# VCU_itr2.net
KiCad netlist of a schematic drawn in EAGLE
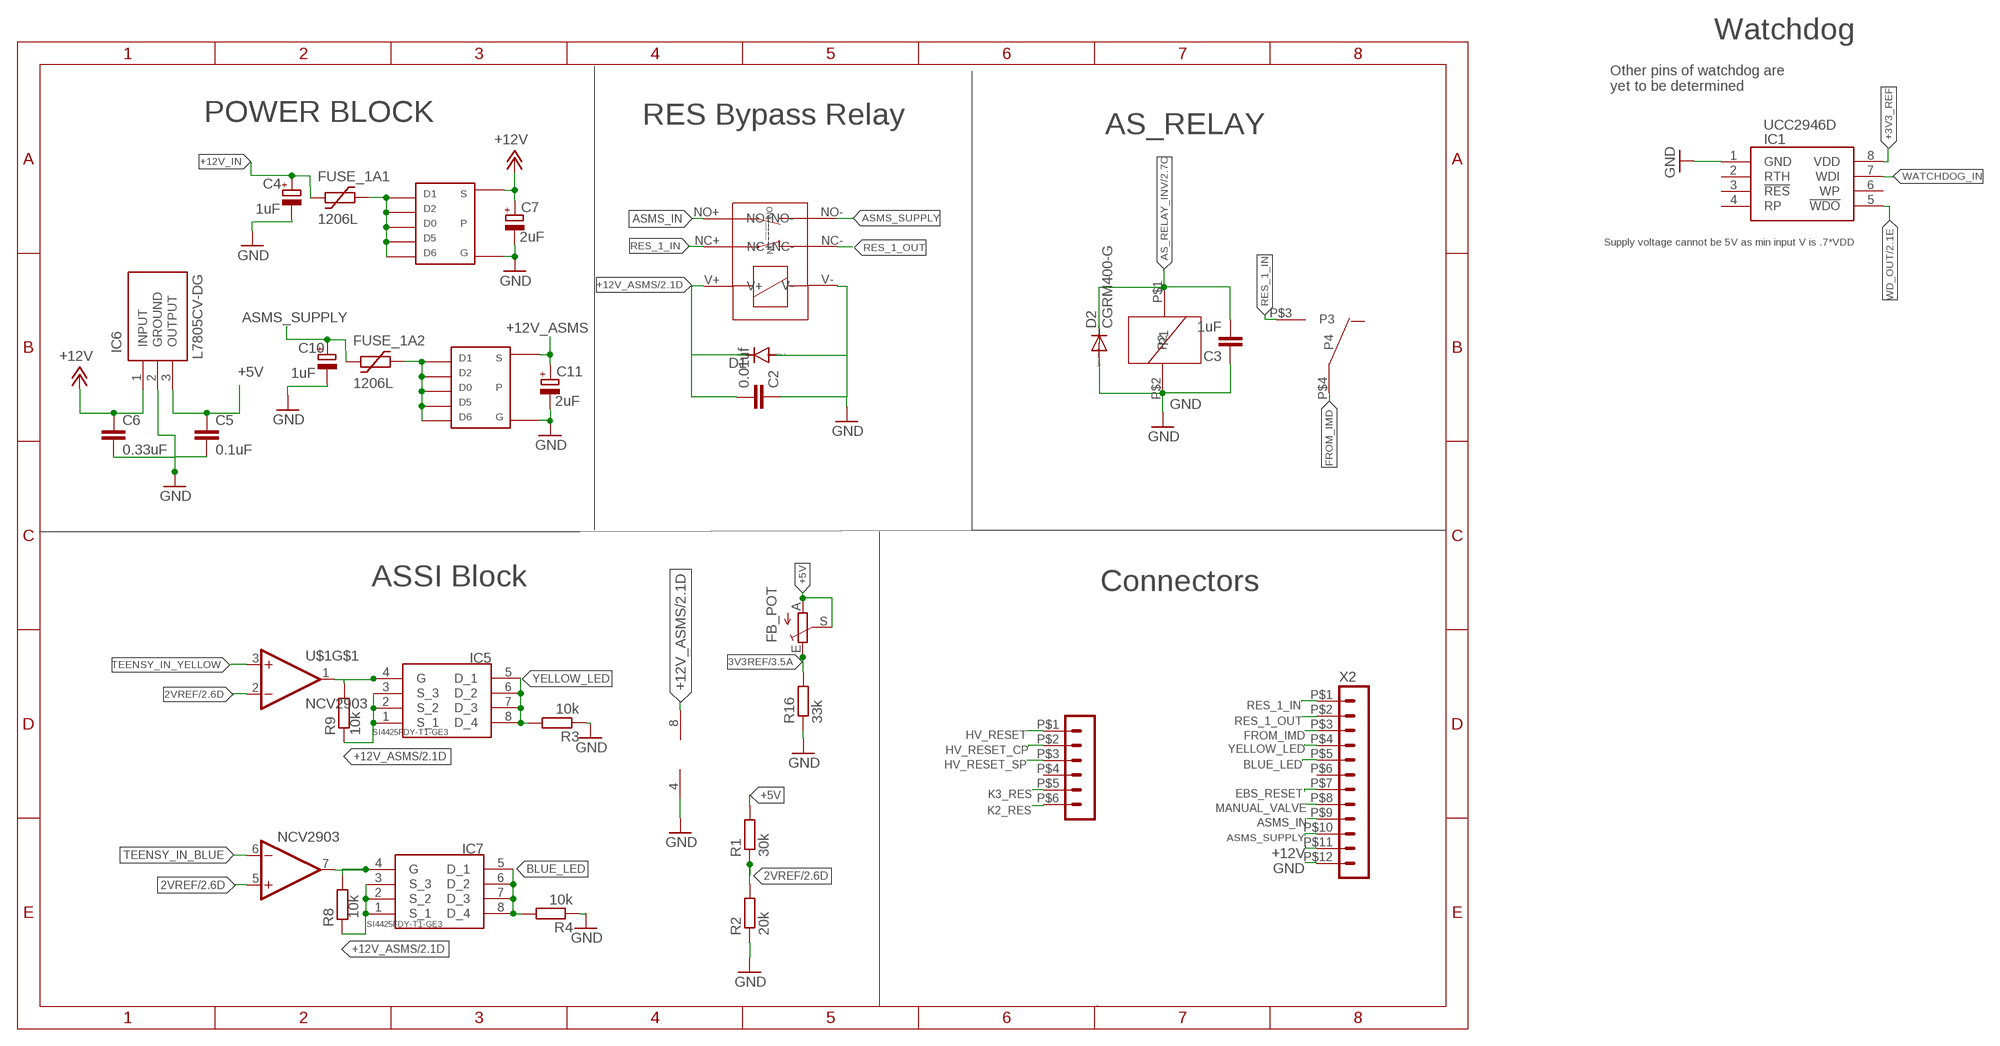
[diagram p0: schematic, sheet 1]
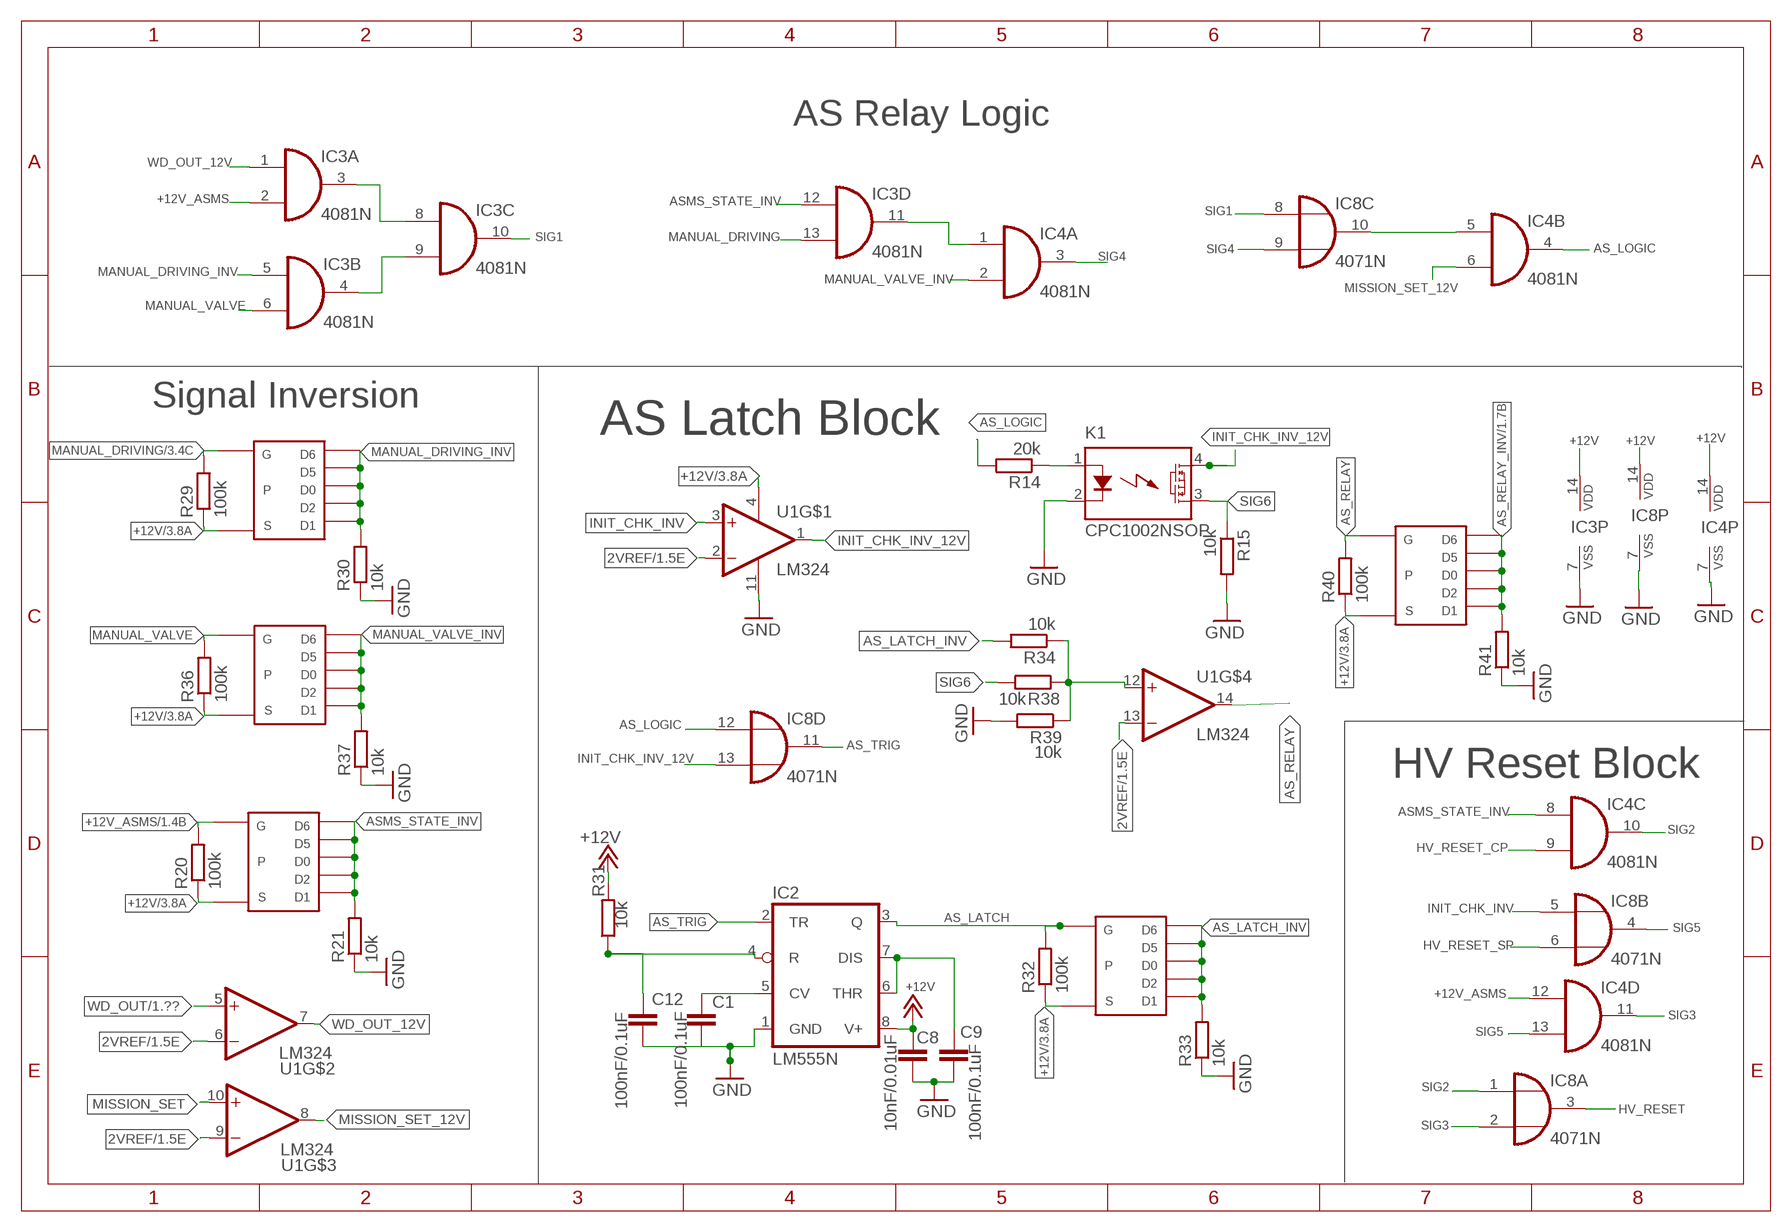
[diagram p1: schematic, sheet 2]
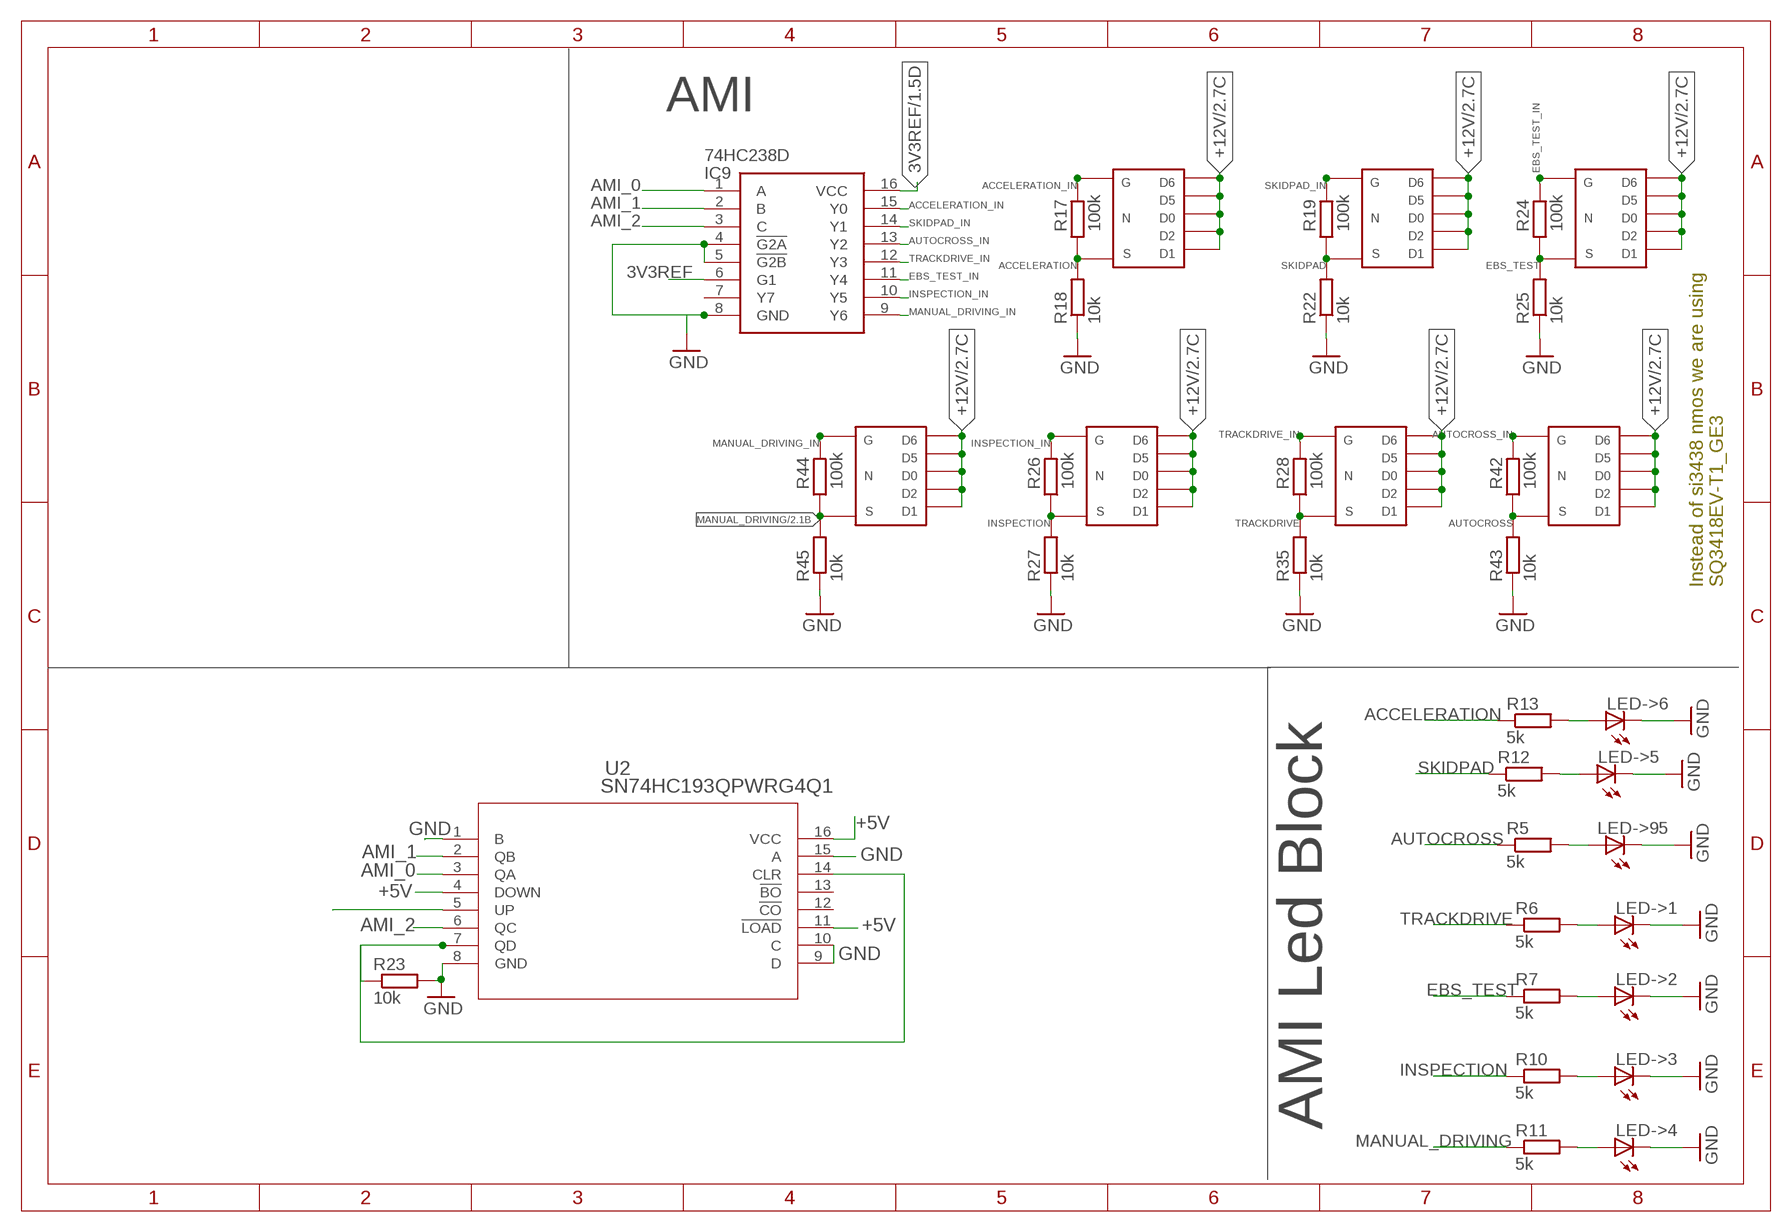
[diagram p2: schematic, sheet 3]
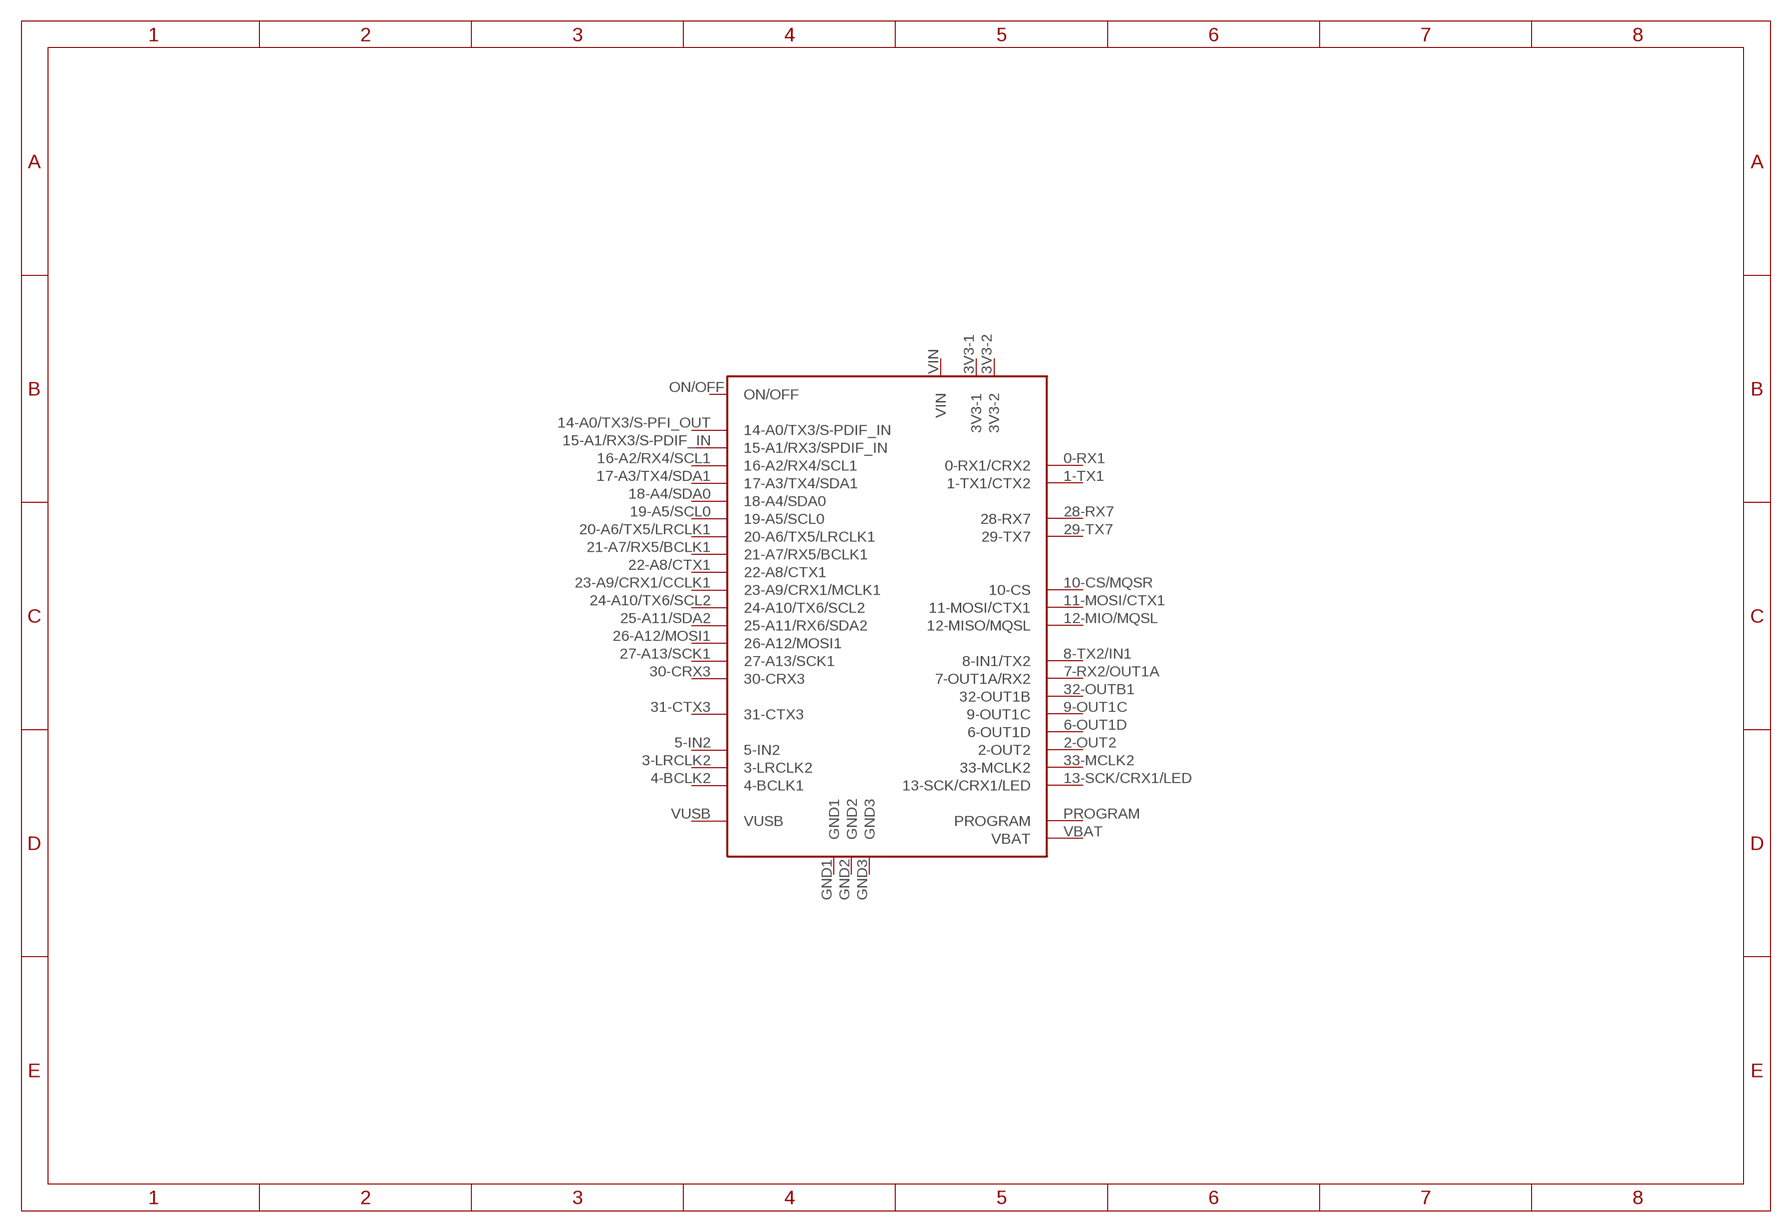
[diagram p3: schematic, sheet 4]

(export (version "E")
  (design (tool "Eeschema 10.0.6"))
  (components
    (comp (ref "IC9")
      (value "74HC238D")
      (footprint "eagle-import:SOIC127P600X175-16N")
      (fields (field (name "MOUSER_PART_NUMBER") "757-74HC238D"))
      (libsource (lib "eagle-import") (part "74HC238D"))
    )
    (comp (ref "LED->1")
      (value "LED-FKIT-1206")
      (footprint "eagle-import:FKIT-LED-1206")
      (libsource (lib "eagle-import") (part "LED-FKIT-1206"))
    )
    (comp (ref "LED->2")
      (value "LED-FKIT-1206")
      (footprint "eagle-import:FKIT-LED-1206")
      (libsource (lib "eagle-import") (part "LED-FKIT-1206"))
    )
    (comp (ref "LED->3")
      (value "LED-FKIT-1206")
      (footprint "eagle-import:FKIT-LED-1206")
      (libsource (lib "eagle-import") (part "LED-FKIT-1206"))
    )
    (comp (ref "LED->4")
      (value "LED-FKIT-1206")
      (footprint "eagle-import:FKIT-LED-1206")
      (libsource (lib "eagle-import") (part "LED-FKIT-1206"))
    )
    (comp (ref "LED->5")
      (value "LED-FKIT-1206")
      (footprint "eagle-import:FKIT-LED-1206")
      (libsource (lib "eagle-import") (part "LED-FKIT-1206"))
    )
    (comp (ref "LED->6")
      (value "LED-FKIT-1206")
      (footprint "eagle-import:FKIT-LED-1206")
      (libsource (lib "eagle-import") (part "LED-FKIT-1206"))
    )
    (comp (ref "LED->95")
      (value "LED-FKIT-1206")
      (footprint "eagle-import:FKIT-LED-1206")
      (libsource (lib "eagle-import") (part "LED-FKIT-1206"))
    )
    (comp (ref "R5")
      (value "5k")
      (footprint "eagle-import:R0805")
      (libsource (lib "eagle-import") (part "R-EU_R0805"))
    )
    (comp (ref "R6")
      (value "5k")
      (footprint "eagle-import:R0805")
      (libsource (lib "eagle-import") (part "R-EU_R0805"))
    )
    (comp (ref "R7")
      (value "5k")
      (footprint "eagle-import:R0805")
      (libsource (lib "eagle-import") (part "R-EU_R0805"))
    )
    (comp (ref "R10")
      (value "5k")
      (footprint "eagle-import:R0805")
      (libsource (lib "eagle-import") (part "R-EU_R0805"))
    )
    (comp (ref "R11")
      (value "5k")
      (footprint "eagle-import:R0805")
      (libsource (lib "eagle-import") (part "R-EU_R0805"))
    )
    (comp (ref "R12")
      (value "5k")
      (footprint "eagle-import:R0805")
      (libsource (lib "eagle-import") (part "R-EU_R0805"))
    )
    (comp (ref "R13")
      (value "5k")
      (footprint "eagle-import:R0805")
      (libsource (lib "eagle-import") (part "R-EU_R0805"))
    )
    (comp (ref "R17")
      (value "100k")
      (footprint "eagle-import:R0805")
      (libsource (lib "eagle-import") (part "R-EU_R0805"))
    )
    (comp (ref "R18")
      (value "10k")
      (footprint "eagle-import:M0805")
      (libsource (lib "eagle-import") (part "IIT_BOMBAY_Racing2_R-EU_M0805"))
    )
    (comp (ref "R19")
      (value "100k")
      (footprint "eagle-import:R0805")
      (libsource (lib "eagle-import") (part "R-EU_R0805"))
    )
    (comp (ref "R22")
      (value "10k")
      (footprint "eagle-import:M0805")
      (libsource (lib "eagle-import") (part "IIT_BOMBAY_Racing2_R-EU_M0805"))
    )
    (comp (ref "R23")
      (value "10k")
      (footprint "eagle-import:M0805")
      (libsource (lib "eagle-import") (part "IIT_BOMBAY_Racing2_R-EU_M0805"))
    )
    (comp (ref "R24")
      (value "100k")
      (footprint "eagle-import:R0805")
      (libsource (lib "eagle-import") (part "R-EU_R0805"))
    )
    (comp (ref "R25")
      (value "10k")
      (footprint "eagle-import:M0805")
      (libsource (lib "eagle-import") (part "IIT_BOMBAY_Racing2_R-EU_M0805"))
    )
    (comp (ref "R26")
      (value "100k")
      (footprint "eagle-import:R0805")
      (libsource (lib "eagle-import") (part "R-EU_R0805"))
    )
    (comp (ref "R27")
      (value "10k")
      (footprint "eagle-import:M0805")
      (libsource (lib "eagle-import") (part "IIT_BOMBAY_Racing2_R-EU_M0805"))
    )
    (comp (ref "R28")
      (value "100k")
      (footprint "eagle-import:R0805")
      (libsource (lib "eagle-import") (part "R-EU_R0805"))
    )
    (comp (ref "R35")
      (value "10k")
      (footprint "eagle-import:M0805")
      (libsource (lib "eagle-import") (part "IIT_BOMBAY_Racing2_R-EU_M0805"))
    )
    (comp (ref "R42")
      (value "100k")
      (footprint "eagle-import:R0805")
      (libsource (lib "eagle-import") (part "R-EU_R0805"))
    )
    (comp (ref "R43")
      (value "10k")
      (footprint "eagle-import:M0805")
      (libsource (lib "eagle-import") (part "IIT_BOMBAY_Racing2_R-EU_M0805"))
    )
    (comp (ref "R44")
      (value "100k")
      (footprint "eagle-import:R0805")
      (libsource (lib "eagle-import") (part "R-EU_R0805"))
    )
    (comp (ref "R45")
      (value "10k")
      (footprint "eagle-import:M0805")
      (libsource (lib "eagle-import") (part "IIT_BOMBAY_Racing2_R-EU_M0805"))
    )
    (comp (ref "U$13")
      (value "TSOP-6_NMOS")
      (footprint "eagle-import:TSOP-6_NMOS")
      (libsource (lib "eagle-import") (part "TSOP-6_NMOS"))
    )
    (comp (ref "U$14")
      (value "TSOP-6_NMOS")
      (footprint "eagle-import:TSOP-6_NMOS")
      (libsource (lib "eagle-import") (part "TSOP-6_NMOS"))
    )
    (comp (ref "U$15")
      (value "TSOP-6_NMOS")
      (footprint "eagle-import:TSOP-6_NMOS")
      (libsource (lib "eagle-import") (part "TSOP-6_NMOS"))
    )
    (comp (ref "U$16")
      (value "TSOP-6_NMOS")
      (footprint "eagle-import:TSOP-6_NMOS")
      (libsource (lib "eagle-import") (part "TSOP-6_NMOS"))
    )
    (comp (ref "U$17")
      (value "TSOP-6_NMOS")
      (footprint "eagle-import:TSOP-6_NMOS")
      (libsource (lib "eagle-import") (part "TSOP-6_NMOS"))
    )
    (comp (ref "U$18")
      (value "TSOP-6_NMOS")
      (footprint "eagle-import:TSOP-6_NMOS")
      (libsource (lib "eagle-import") (part "TSOP-6_NMOS"))
    )
    (comp (ref "U$19")
      (value "TSOP-6_NMOS")
      (footprint "eagle-import:TSOP-6_NMOS")
      (libsource (lib "eagle-import") (part "TSOP-6_NMOS"))
    )
    (comp (ref "U2")
      (value "SN74HC193QPWRG4Q1")
      (footprint "eagle-import:PW16")
      (fields (field (name "COPYRIGHT") "Copyright (C) 2024 Ultra Librarian. All rights reserved."))
      (libsource (lib "eagle-import") (part "SN74HC193QPWRG4Q1"))
    )
    (comp (ref "C1")
      (value "100nF/0.1uF")
      (footprint "eagle-import:C0805")
      (libsource (lib "eagle-import") (part "C-EUC0805"))
    )
    (comp (ref "C8")
      (value "10nF/0.01uF")
      (footprint "eagle-import:C0805")
      (libsource (lib "eagle-import") (part "C-EUC0805"))
    )
    (comp (ref "C9")
      (value "100nF/0.1uF")
      (footprint "eagle-import:C0805")
      (libsource (lib "eagle-import") (part "C-EUC0805"))
    )
    (comp (ref "C12")
      (value "100nF/0.1uF")
      (footprint "eagle-import:C0805")
      (libsource (lib "eagle-import") (part "C-EUC0805"))
    )
    (comp (ref "IC2")
      (value "LM555N")
      (footprint "eagle-import:DIL08")
      (libsource (lib "eagle-import") (part "555NLM"))
    )
    (comp (ref "IC3")
      (value "4081N")
      (footprint "eagle-import:DIL14")
      (libsource (lib "eagle-import") (part "4081N"))
    )
    (comp (ref "IC4")
      (value "4081N")
      (footprint "eagle-import:DIL14")
      (libsource (lib "eagle-import") (part "4081N"))
    )
    (comp (ref "IC8")
      (value "4071N")
      (footprint "eagle-import:DIL14")
      (libsource (lib "eagle-import") (part "4071N"))
    )
    (comp (ref "K1")
      (value "CPC1002NSOP")
      (footprint "eagle-import:SOP04")
      (libsource (lib "eagle-import") (part "CPC1002NSOP"))
    )
    (comp (ref "R14")
      (value "20k")
      (footprint "eagle-import:R0805")
      (libsource (lib "eagle-import") (part "R-EU_R0805"))
    )
    (comp (ref "R15")
      (value "10k")
      (footprint "eagle-import:R0805")
      (libsource (lib "eagle-import") (part "R-EU_R0805"))
    )
    (comp (ref "R20")
      (value "100k")
      (footprint "eagle-import:M0805")
      (libsource (lib "eagle-import") (part "IIT_BOMBAY_Racing2_R-EU_M0805"))
    )
    (comp (ref "R21")
      (value "10k")
      (footprint "eagle-import:M0805")
      (libsource (lib "eagle-import") (part "IIT_BOMBAY_Racing2_R-EU_M0805"))
    )
    (comp (ref "R29")
      (value "100k")
      (footprint "eagle-import:M0805")
      (libsource (lib "eagle-import") (part "IIT_BOMBAY_Racing2_R-EU_M0805"))
    )
    (comp (ref "R30")
      (value "10k")
      (footprint "eagle-import:M0805")
      (libsource (lib "eagle-import") (part "IIT_BOMBAY_Racing2_R-EU_M0805"))
    )
    (comp (ref "R31")
      (value "10k")
      (footprint "eagle-import:R0805")
      (libsource (lib "eagle-import") (part "R-EU_R0805"))
    )
    (comp (ref "R32")
      (value "100k")
      (footprint "eagle-import:M0805")
      (libsource (lib "eagle-import") (part "IIT_BOMBAY_Racing2_R-EU_M0805"))
    )
    (comp (ref "R33")
      (value "10k")
      (footprint "eagle-import:M0805")
      (libsource (lib "eagle-import") (part "IIT_BOMBAY_Racing2_R-EU_M0805"))
    )
    (comp (ref "R34")
      (value "10k")
      (footprint "eagle-import:M0805")
      (libsource (lib "eagle-import") (part "IIT_BOMBAY_Racing2_R-EU_M0805"))
    )
    (comp (ref "R36")
      (value "100k")
      (footprint "eagle-import:M0805")
      (libsource (lib "eagle-import") (part "IIT_BOMBAY_Racing2_R-EU_M0805"))
    )
    (comp (ref "R37")
      (value "10k")
      (footprint "eagle-import:M0805")
      (libsource (lib "eagle-import") (part "IIT_BOMBAY_Racing2_R-EU_M0805"))
    )
    (comp (ref "R38")
      (value "10k")
      (footprint "eagle-import:M0805")
      (libsource (lib "eagle-import") (part "IIT_BOMBAY_Racing2_R-EU_M0805"))
    )
    (comp (ref "R39")
      (value "10k")
      (footprint "eagle-import:M0805")
      (libsource (lib "eagle-import") (part "IIT_BOMBAY_Racing2_R-EU_M0805"))
    )
    (comp (ref "R40")
      (value "100k")
      (footprint "eagle-import:M0805")
      (libsource (lib "eagle-import") (part "IIT_BOMBAY_Racing2_R-EU_M0805"))
    )
    (comp (ref "R41")
      (value "10k")
      (footprint "eagle-import:M0805")
      (libsource (lib "eagle-import") (part "IIT_BOMBAY_Racing2_R-EU_M0805"))
    )
    (comp (ref "SI2")
      (value "TSOP-6_PMOS")
      (footprint "eagle-import:TSOP-6_PMOS")
      (libsource (lib "eagle-import") (part "TSOP-6_PMOS"))
    )
    (comp (ref "SI3")
      (value "TSOP-6_PMOS")
      (footprint "eagle-import:TSOP-6_PMOS")
      (libsource (lib "eagle-import") (part "TSOP-6_PMOS"))
    )
    (comp (ref "SI5")
      (value "TSOP-6_PMOS")
      (footprint "eagle-import:TSOP-6_PMOS")
      (libsource (lib "eagle-import") (part "TSOP-6_PMOS"))
    )
    (comp (ref "SI6")
      (value "TSOP-6_PMOS")
      (footprint "eagle-import:TSOP-6_PMOS")
      (libsource (lib "eagle-import") (part "TSOP-6_PMOS"))
    )
    (comp (ref "SI7")
      (value "TSOP-6_PMOS")
      (footprint "eagle-import:TSOP-6_PMOS")
      (libsource (lib "eagle-import") (part "TSOP-6_PMOS"))
    )
    (comp (ref "U1")
      (value "LM324")
      (footprint "eagle-import:SOIC127P600X175-14N")
      (description "Quad OpAmp")
      (fields (field (name "MF") "Intersil") (field (name "MP") "LM324.."))
      (libsource (lib "eagle-import") (part "LM324"))
    )
    (comp (ref "BMS-CONN7")
      (value "HEADER_POS6_43045-0612")
      (footprint "eagle-import:43045-0612")
      (libsource (lib "eagle-import") (part "HEADER_POS6_?43045-0612"))
    )
    (comp (ref "C2")
      (value "0.01uf")
      (footprint "eagle-import:C1210")
      (libsource (lib "eagle-import") (part "C-EUC1210"))
    )
    (comp (ref "C3")
      (value "1uF")
      (footprint "eagle-import:C0805")
      (libsource (lib "eagle-import") (part "C-EUC0805"))
    )
    (comp (ref "C4")
      (value "1uF")
      (footprint "eagle-import:SMC_A")
      (libsource (lib "eagle-import") (part "CPOL-EUSMCA"))
    )
    (comp (ref "C5")
      (value "0.1uF")
      (footprint "eagle-import:C0805")
      (libsource (lib "eagle-import") (part "rcl_334_C-EUC0805"))
    )
    (comp (ref "C6")
      (value "0.33uF")
      (footprint "eagle-import:C0805")
      (libsource (lib "eagle-import") (part "rcl_334_C-EUC0805"))
    )
    (comp (ref "C7")
      (value "2uF")
      (footprint "eagle-import:E2,5-6")
      (libsource (lib "eagle-import") (part "CPOL-EUE2.5-6"))
    )
    (comp (ref "C10")
      (value "1uF")
      (footprint "eagle-import:SMC_A")
      (libsource (lib "eagle-import") (part "CPOL-EUSMCA"))
    )
    (comp (ref "C11")
      (value "2uF")
      (footprint "eagle-import:E2,5-6")
      (libsource (lib "eagle-import") (part "CPOL-EUE2.5-6"))
    )
    (comp (ref "D1")
      (value "DIODE-DO214AC")
      (footprint "eagle-import:DO214AC")
      (libsource (lib "eagle-import") (part "DIODE-DO214AC"))
    )
    (comp (ref "D2")
      (value "CGRM400-G")
      (footprint "eagle-import:SOD-123_MINI-SMA")
      (libsource (lib "eagle-import") (part "CGRM400-G"))
    )
    (comp (ref "FB_POT")
      (value "17k")
      (footprint "eagle-import:S63S")
      (libsource (lib "eagle-import") (part "TRIM_EU-S63S"))
    )
    (comp (ref "FUSE_1A1")
      (value "1206L")
      (footprint "eagle-import:1206L")
      (libsource (lib "eagle-import") (part "1206L"))
    )
    (comp (ref "FUSE_1A2")
      (value "1206L")
      (footprint "eagle-import:1206L")
      (libsource (lib "eagle-import") (part "1206L"))
    )
    (comp (ref "IC1")
      (value "UCC2946D")
      (footprint "eagle-import:SOIC127P600X175-8N")
      (fields (field (name "MOUSER_PART_NUMBER") "595-UCC2946D"))
      (libsource (lib "eagle-import") (part "UCC2946D"))
    )
    (comp (ref "IC5")
      (value "SI4425FDY-T1-GE3")
      (footprint "eagle-import:SOIC127P600X175-8N")
      (fields (field (name "MOUSER_PART_NUMBER") "78-SI4425FDY-T1-GE3"))
      (libsource (lib "eagle-import") (part "SI4425FDY-T1-GE3"))
    )
    (comp (ref "IC6")
      (value "L7805CV-DG")
      (footprint "eagle-import:TO255P460X1020X2008-3P")
      (fields (field (name "MOUSER_PART_NUMBER") "511-L7805CV-DG"))
      (libsource (lib "eagle-import") (part "L7805CV-DG"))
    )
    (comp (ref "IC7")
      (value "SI4425FDY-T1-GE3")
      (footprint "eagle-import:SOIC127P600X175-8N")
      (fields (field (name "MOUSER_PART_NUMBER") "78-SI4425FDY-T1-GE3"))
      (libsource (lib "eagle-import") (part "SI4425FDY-T1-GE3"))
    )
    (comp (ref "R1")
      (value "30k")
      (footprint "eagle-import:M0805")
      (libsource (lib "eagle-import") (part "IIT_BOMBAY_Racing2_R-EU_M0805"))
    )
    (comp (ref "R2")
      (value "20k")
      (footprint "eagle-import:M0805")
      (libsource (lib "eagle-import") (part "IIT_BOMBAY_Racing2_R-EU_M0805"))
    )
    (comp (ref "R3")
      (value "10k")
      (footprint "eagle-import:M0805")
      (libsource (lib "eagle-import") (part "IIT_BOMBAY_Racing2_R-EU_M0805"))
    )
    (comp (ref "R4")
      (value "10k")
      (footprint "eagle-import:M0805")
      (libsource (lib "eagle-import") (part "IIT_BOMBAY_Racing2_R-EU_M0805"))
    )
    (comp (ref "R8")
      (value "10k")
      (footprint "eagle-import:M0805")
      (libsource (lib "eagle-import") (part "IIT_BOMBAY_Racing2_R-EU_M0805"))
    )
    (comp (ref "R9")
      (value "10k")
      (footprint "eagle-import:M0805")
      (libsource (lib "eagle-import") (part "IIT_BOMBAY_Racing2_R-EU_M0805"))
    )
    (comp (ref "R16")
      (value "33k")
      (footprint "eagle-import:M0805")
      (libsource (lib "eagle-import") (part "IIT_BOMBAY_Racing2_R-EU_M0805"))
    )
    (comp (ref "SI1")
      (value "TSOP-6_PMOS")
      (footprint "eagle-import:TSOP-6_PMOS")
      (libsource (lib "eagle-import") (part "TSOP-6_PMOS"))
    )
    (comp (ref "SI4")
      (value "TSOP-6_PMOS")
      (footprint "eagle-import:TSOP-6_PMOS")
      (libsource (lib "eagle-import") (part "TSOP-6_PMOS"))
    )
    (comp (ref "U$1")
      (value "NCV2903")
      (footprint "eagle-import:SOIC-8")
      (libsource (lib "eagle-import") (part "NCV2903"))
    )
    (comp (ref "U$2")
      (value "G6DN_RELAY")
      (footprint "eagle-import:G6DN_RELAY")
      (libsource (lib "eagle-import") (part "G6DN_RELAY"))
    )
    (comp (ref "U$9")
      (value "SFM_RELAY")
      (footprint "eagle-import:SFM_RELAY")
      (libsource (lib "eagle-import") (part "SFM_RELAY"))
    )
    (comp (ref "X2")
      (value "HEADER_POS12_44914-1201")
      (footprint "eagle-import:44914-1201")
      (libsource (lib "eagle-import") (part "HEADER_POS12_?44914-1201"))
    )
    (comp (ref "U$3")
      (value "TEENSY40")
      (footprint "eagle-import:TEENSY40")
      (fields (field (name "SPICEPREFIX") "X"))
      (libsource (lib "eagle-import") (part "TEENSY40"))
    )
  )
  (nets
    (net (code "1") (name "+3V3_REF") (class "Default")
      (node (ref "IC1") (pin "8") (pinfunction "VDD_8") (pintype "bidirectional"))
    )
    (net (code "2") (name "+5V") (class "Default")
      (node (ref "C5") (pin "1") (pinfunction "1_1") (pintype "passive"))
      (node (ref "FB_POT") (pin "A") (pinfunction "A_A") (pintype "passive"))
      (node (ref "FB_POT") (pin "S") (pinfunction "S_S") (pintype "passive"))
      (node (ref "IC6") (pin "3") (pinfunction "OUTPUT_3") (pintype "bidirectional"))
      (node (ref "R1") (pin "2") (pinfunction "2_2") (pintype "passive"))
      (node (ref "U2") (pin "11") (pinfunction "~{LOAD}_11") (pintype "input"))
      (node (ref "U2") (pin "16") (pinfunction "VCC_16") (pintype "power_in"))
      (node (ref "U2") (pin "4") (pinfunction "DOWN_4") (pintype "passive"))
    )
    (net (code "3") (name "+12V") (class "Default")
      (node (ref "C6") (pin "1") (pinfunction "1_1") (pintype "passive"))
      (node (ref "C7") (pin "+") (pinfunction "+_+") (pintype "passive"))
      (node (ref "C8") (pin "1") (pinfunction "1_1") (pintype "passive"))
      (node (ref "IC2") (pin "8") (pinfunction "V+_8") (pintype "power_in"))
      (node (ref "IC3") (pin "14") (pinfunction "VDD_14") (pintype "power_in"))
      (node (ref "IC4") (pin "14") (pinfunction "VDD_14") (pintype "power_in"))
      (node (ref "IC6") (pin "1") (pinfunction "INPUT_1") (pintype "bidirectional"))
      (node (ref "IC8") (pin "14") (pinfunction "VDD_14") (pintype "power_in"))
      (node (ref "R20") (pin "1") (pinfunction "1_1") (pintype "passive"))
      (node (ref "R29") (pin "1") (pinfunction "1_1") (pintype "passive"))
      (node (ref "R31") (pin "2") (pinfunction "2_2") (pintype "passive"))
      (node (ref "R32") (pin "1") (pinfunction "1_1") (pintype "passive"))
      (node (ref "R36") (pin "1") (pinfunction "1_1") (pintype "passive"))
      (node (ref "R40") (pin "1") (pinfunction "1_1") (pintype "passive"))
      (node (ref "SI1") (pin "S") (pinfunction "S_S") (pintype "bidirectional"))
      (node (ref "SI2") (pin "S") (pinfunction "S_S") (pintype "bidirectional"))
      (node (ref "SI3") (pin "S") (pinfunction "S_S") (pintype "bidirectional"))
      (node (ref "SI5") (pin "S") (pinfunction "S_S") (pintype "bidirectional"))
      (node (ref "SI6") (pin "S") (pinfunction "S_S") (pintype "bidirectional"))
      (node (ref "SI7") (pin "S") (pinfunction "S_S") (pintype "bidirectional"))
      (node (ref "U$13") (pin "1") (pinfunction "1_1") (pintype "bidirectional"))
      (node (ref "U$13") (pin "2") (pinfunction "2_2") (pintype "bidirectional"))
      (node (ref "U$13") (pin "5") (pinfunction "5_5") (pintype "bidirectional"))
      (node (ref "U$13") (pin "6") (pinfunction "6_6") (pintype "bidirectional"))
      (node (ref "U$13") (pin "D") (pinfunction "D0_D") (pintype "bidirectional"))
      (node (ref "U$14") (pin "1") (pinfunction "1_1") (pintype "bidirectional"))
      (node (ref "U$14") (pin "2") (pinfunction "2_2") (pintype "bidirectional"))
      (node (ref "U$14") (pin "5") (pinfunction "5_5") (pintype "bidirectional"))
      (node (ref "U$14") (pin "6") (pinfunction "6_6") (pintype "bidirectional"))
      (node (ref "U$14") (pin "D") (pinfunction "D0_D") (pintype "bidirectional"))
      (node (ref "U$15") (pin "1") (pinfunction "1_1") (pintype "bidirectional"))
      (node (ref "U$15") (pin "2") (pinfunction "2_2") (pintype "bidirectional"))
      (node (ref "U$15") (pin "5") (pinfunction "5_5") (pintype "bidirectional"))
      (node (ref "U$15") (pin "6") (pinfunction "6_6") (pintype "bidirectional"))
      (node (ref "U$15") (pin "D") (pinfunction "D0_D") (pintype "bidirectional"))
      (node (ref "U$16") (pin "1") (pinfunction "1_1") (pintype "bidirectional"))
      (node (ref "U$16") (pin "2") (pinfunction "2_2") (pintype "bidirectional"))
      (node (ref "U$16") (pin "5") (pinfunction "5_5") (pintype "bidirectional"))
      (node (ref "U$16") (pin "6") (pinfunction "6_6") (pintype "bidirectional"))
      (node (ref "U$16") (pin "D") (pinfunction "D0_D") (pintype "bidirectional"))
      (node (ref "U$17") (pin "1") (pinfunction "1_1") (pintype "bidirectional"))
      (node (ref "U$17") (pin "2") (pinfunction "2_2") (pintype "bidirectional"))
      (node (ref "U$17") (pin "5") (pinfunction "5_5") (pintype "bidirectional"))
      (node (ref "U$17") (pin "6") (pinfunction "6_6") (pintype "bidirectional"))
      (node (ref "U$17") (pin "D") (pinfunction "D0_D") (pintype "bidirectional"))
      (node (ref "U$18") (pin "1") (pinfunction "1_1") (pintype "bidirectional"))
      (node (ref "U$18") (pin "2") (pinfunction "2_2") (pintype "bidirectional"))
      (node (ref "U$18") (pin "5") (pinfunction "5_5") (pintype "bidirectional"))
      (node (ref "U$18") (pin "6") (pinfunction "6_6") (pintype "bidirectional"))
      (node (ref "U$18") (pin "D") (pinfunction "D0_D") (pintype "bidirectional"))
      (node (ref "U$19") (pin "1") (pinfunction "1_1") (pintype "bidirectional"))
      (node (ref "U$19") (pin "2") (pinfunction "2_2") (pintype "bidirectional"))
      (node (ref "U$19") (pin "5") (pinfunction "5_5") (pintype "bidirectional"))
      (node (ref "U$19") (pin "6") (pinfunction "6_6") (pintype "bidirectional"))
      (node (ref "U$19") (pin "D") (pinfunction "D0_D") (pintype "bidirectional"))
      (node (ref "U1") (pin "4") (pinfunction "VCC+_4") (pintype "power_in"))
      (node (ref "X2") (pin "P$11") (pinfunction "11_P$11") (pintype "passive"))
    )
    (net (code "4") (name "+12V_ASMS") (class "Default")
      (node (ref "C11") (pin "+") (pinfunction "+_+") (pintype "passive"))
      (node (ref "C2") (pin "2") (pinfunction "2_2") (pintype "passive"))
      (node (ref "D1") (pin "C") (pinfunction "C_C") (pintype "passive"))
      (node (ref "IC3") (pin "2") (pinfunction "I1_2") (pintype "input"))
      (node (ref "IC4") (pin "12") (pinfunction "I0_12") (pintype "input"))
      (node (ref "IC5") (pin "1") (pinfunction "S_1_1") (pintype "bidirectional"))
      (node (ref "IC5") (pin "2") (pinfunction "S_2_2") (pintype "bidirectional"))
      (node (ref "IC5") (pin "3") (pinfunction "S_3_3") (pintype "bidirectional"))
      (node (ref "IC7") (pin "1") (pinfunction "S_1_1") (pintype "bidirectional"))
      (node (ref "IC7") (pin "2") (pinfunction "S_2_2") (pintype "bidirectional"))
      (node (ref "IC7") (pin "3") (pinfunction "S_3_3") (pintype "bidirectional"))
      (node (ref "R20") (pin "2") (pinfunction "2_2") (pintype "passive"))
      (node (ref "R8") (pin "1") (pinfunction "1_1") (pintype "passive"))
      (node (ref "R9") (pin "1") (pinfunction "1_1") (pintype "passive"))
      (node (ref "SI4") (pin "S") (pinfunction "S_S") (pintype "bidirectional"))
      (node (ref "SI5") (pin "G") (pinfunction "G_G") (pintype "bidirectional"))
      (node (ref "U$1") (pin "8") (pinfunction "V+_8") (pintype "power_in"))
      (node (ref "U$9") (pin "V+") (pinfunction "V+_V+") (pintype "bidirectional"))
    )
    (net (code "5") (name "+12V_IN") (class "Default")
      (node (ref "C4") (pin "+") (pinfunction "+_+") (pintype "passive"))
      (node (ref "FUSE_1A1") (pin "P$1") (pinfunction "1_P$1") (pintype "passive"))
    )
    (net (code "6") (name "2VREF") (class "Default")
      (node (ref "R1") (pin "1") (pinfunction "1_1") (pintype "passive"))
      (node (ref "R2") (pin "2") (pinfunction "2_2") (pintype "passive"))
      (node (ref "U$1") (pin "2") (pinfunction "-IN_2") (pintype "input"))
      (node (ref "U$1") (pin "5") (pinfunction "+IN_5") (pintype "input"))
      (node (ref "U1") (pin "13") (pinfunction "INVERTING_INPUT4_13") (pintype "input"))
      (node (ref "U1") (pin "2") (pinfunction "INVERTING_INPUT1_2") (pintype "input"))
      (node (ref "U1") (pin "6") (pinfunction "INVERTING_INPUT2_6") (pintype "input"))
      (node (ref "U1") (pin "9") (pinfunction "INVERTING_INPUT3_9") (pintype "input"))
    )
    (net (code "7") (name "3V3REF") (class "Default")
      (node (ref "FB_POT") (pin "E") (pinfunction "E_E") (pintype "passive"))
      (node (ref "IC9") (pin "16") (pinfunction "VCC_16") (pintype "bidirectional"))
      (node (ref "IC9") (pin "6") (pinfunction "G1_6") (pintype "bidirectional"))
      (node (ref "R16") (pin "2") (pinfunction "2_2") (pintype "passive"))
    )
    (net (code "8") (name "ACCELERATION") (class "Default")
      (node (ref "R13") (pin "1") (pinfunction "1_1") (pintype "passive"))
      (node (ref "R17") (pin "1") (pinfunction "1_1") (pintype "passive"))
      (node (ref "R18") (pin "2") (pinfunction "2_2") (pintype "passive"))
      (node (ref "U$13") (pin "S") (pinfunction "S_S") (pintype "bidirectional"))
    )
    (net (code "9") (name "ACCELERATION_IN") (class "Default")
      (node (ref "IC9") (pin "15") (pinfunction "Y0_15") (pintype "bidirectional"))
      (node (ref "R17") (pin "2") (pinfunction "2_2") (pintype "passive"))
      (node (ref "U$13") (pin "G") (pinfunction "G_G") (pintype "bidirectional"))
    )
    (net (code "10") (name "AMI_0") (class "Default")
      (node (ref "IC9") (pin "1") (pinfunction "A_1") (pintype "bidirectional"))
      (node (ref "U2") (pin "3") (pinfunction "QA_3") (pintype "output"))
    )
    (net (code "11") (name "AMI_1") (class "Default")
      (node (ref "IC9") (pin "2") (pinfunction "B_2") (pintype "bidirectional"))
      (node (ref "U2") (pin "2") (pinfunction "QB_2") (pintype "output"))
    )
    (net (code "12") (name "AMI_2") (class "Default")
      (node (ref "IC9") (pin "3") (pinfunction "C_3") (pintype "bidirectional"))
      (node (ref "U2") (pin "6") (pinfunction "QC_6") (pintype "output"))
    )
    (net (code "13") (name "ASMS_IN") (class "Default")
      (node (ref "U$9") (pin "NO+") (pinfunction "NO+_NO+") (pintype "bidirectional"))
      (node (ref "X2") (pin "P$9") (pinfunction "9_P$9") (pintype "passive"))
    )
    (net (code "14") (name "ASMS_STATE_INV") (class "Default")
      (node (ref "IC3") (pin "12") (pinfunction "I0_12") (pintype "input"))
      (node (ref "IC4") (pin "8") (pinfunction "I0_8") (pintype "input"))
      (node (ref "R21") (pin "2") (pinfunction "2_2") (pintype "passive"))
      (node (ref "SI5") (pin "1") (pinfunction "1_1") (pintype "bidirectional"))
      (node (ref "SI5") (pin "2") (pinfunction "2_2") (pintype "bidirectional"))
      (node (ref "SI5") (pin "5") (pinfunction "5_5") (pintype "bidirectional"))
      (node (ref "SI5") (pin "6") (pinfunction "6_6") (pintype "bidirectional"))
      (node (ref "SI5") (pin "D") (pinfunction "D0_D") (pintype "bidirectional"))
    )
    (net (code "15") (name "ASMS_SUPPLY") (class "Default")
      (node (ref "C10") (pin "+") (pinfunction "+_+") (pintype "passive"))
      (node (ref "FUSE_1A2") (pin "P$1") (pinfunction "1_P$1") (pintype "passive"))
      (node (ref "U$9") (pin "NO-") (pinfunction "NO-_NO-") (pintype "bidirectional"))
      (node (ref "X2") (pin "P$10") (pinfunction "10_P$10") (pintype "passive"))
    )
    (net (code "16") (name "AS_LATCH") (class "Default")
      (node (ref "IC2") (pin "3") (pinfunction "Q_3") (pintype "output"))
      (node (ref "R32") (pin "2") (pinfunction "2_2") (pintype "passive"))
      (node (ref "SI2") (pin "G") (pinfunction "G_G") (pintype "bidirectional"))
    )
    (net (code "17") (name "AS_LATCH_INV") (class "Default")
      (node (ref "R33") (pin "2") (pinfunction "2_2") (pintype "passive"))
      (node (ref "R34") (pin "2") (pinfunction "2_2") (pintype "passive"))
      (node (ref "SI2") (pin "1") (pinfunction "1_1") (pintype "bidirectional"))
      (node (ref "SI2") (pin "2") (pinfunction "2_2") (pintype "bidirectional"))
      (node (ref "SI2") (pin "5") (pinfunction "5_5") (pintype "bidirectional"))
      (node (ref "SI2") (pin "6") (pinfunction "6_6") (pintype "bidirectional"))
      (node (ref "SI2") (pin "D") (pinfunction "D0_D") (pintype "bidirectional"))
    )
    (net (code "18") (name "AS_LOGIC") (class "Default")
      (node (ref "IC4") (pin "4") (pinfunction "O_4") (pintype "output"))
      (node (ref "IC8") (pin "12") (pinfunction "I0_12") (pintype "input"))
      (node (ref "R14") (pin "2") (pinfunction "2_2") (pintype "passive"))
    )
    (net (code "19") (name "AS_RELAY") (class "Default")
      (node (ref "R40") (pin "2") (pinfunction "2_2") (pintype "passive"))
      (node (ref "SI3") (pin "G") (pinfunction "G_G") (pintype "bidirectional"))
      (node (ref "U1") (pin "14") (pinfunction "OUTPUT4_14") (pintype "output"))
    )
    (net (code "20") (name "AS_RELAY_INV") (class "Default")
      (node (ref "C3") (pin "2") (pinfunction "2_2") (pintype "passive"))
      (node (ref "D2") (pin "C") (pinfunction "C_C") (pintype "passive"))
      (node (ref "R41") (pin "2") (pinfunction "2_2") (pintype "passive"))
      (node (ref "SI3") (pin "1") (pinfunction "1_1") (pintype "bidirectional"))
      (node (ref "SI3") (pin "2") (pinfunction "2_2") (pintype "bidirectional"))
      (node (ref "SI3") (pin "5") (pinfunction "5_5") (pintype "bidirectional"))
      (node (ref "SI3") (pin "6") (pinfunction "6_6") (pintype "bidirectional"))
      (node (ref "SI3") (pin "D") (pinfunction "D0_D") (pintype "bidirectional"))
      (node (ref "U$2") (pin "P$1") (pinfunction "P1_P$1") (pintype "bidirectional"))
    )
    (net (code "21") (name "AS_TRIG") (class "Default")
      (node (ref "IC2") (pin "2") (pinfunction "TR_2") (pintype "input"))
      (node (ref "IC8") (pin "11") (pinfunction "O_11") (pintype "output"))
    )
    (net (code "22") (name "AUTOCROSS") (class "Default")
      (node (ref "R42") (pin "1") (pinfunction "1_1") (pintype "passive"))
      (node (ref "R43") (pin "2") (pinfunction "2_2") (pintype "passive"))
      (node (ref "R5") (pin "1") (pinfunction "1_1") (pintype "passive"))
      (node (ref "U$18") (pin "S") (pinfunction "S_S") (pintype "bidirectional"))
    )
    (net (code "23") (name "AUTOCROSS_IN") (class "Default")
      (node (ref "IC9") (pin "13") (pinfunction "Y2_13") (pintype "bidirectional"))
      (node (ref "R42") (pin "2") (pinfunction "2_2") (pintype "passive"))
      (node (ref "U$18") (pin "G") (pinfunction "G_G") (pintype "bidirectional"))
    )
    (net (code "24") (name "BLUE_LED") (class "Default")
      (node (ref "IC7") (pin "5") (pinfunction "D_1_5") (pintype "bidirectional"))
      (node (ref "IC7") (pin "6") (pinfunction "D_2_6") (pintype "bidirectional"))
      (node (ref "IC7") (pin "7") (pinfunction "D_3_7") (pintype "bidirectional"))
      (node (ref "IC7") (pin "8") (pinfunction "D_4_8") (pintype "bidirectional"))
      (node (ref "R4") (pin "2") (pinfunction "2_2") (pintype "passive"))
      (node (ref "X2") (pin "P$5") (pinfunction "5_P$5") (pintype "passive"))
    )
    (net (code "25") (name "EBS_RESET") (class "Default")
      (node (ref "X2") (pin "P$7") (pinfunction "7_P$7") (pintype "passive"))
    )
    (net (code "26") (name "EBS_TEST") (class "Default")
      (node (ref "R24") (pin "1") (pinfunction "1_1") (pintype "passive"))
      (node (ref "R25") (pin "2") (pinfunction "2_2") (pintype "passive"))
      (node (ref "R7") (pin "1") (pinfunction "1_1") (pintype "passive"))
      (node (ref "U$15") (pin "S") (pinfunction "S_S") (pintype "bidirectional"))
    )
    (net (code "27") (name "EBS_TEST_IN") (class "Default")
      (node (ref "IC9") (pin "11") (pinfunction "Y4_11") (pintype "bidirectional"))
      (node (ref "R24") (pin "2") (pinfunction "2_2") (pintype "passive"))
      (node (ref "U$15") (pin "G") (pinfunction "G_G") (pintype "bidirectional"))
    )
    (net (code "28") (name "FROM_IMD") (class "Default")
      (node (ref "U$2") (pin "P$4") (pinfunction "P4_P$4") (pintype "bidirectional"))
      (node (ref "X2") (pin "P$3") (pinfunction "3_P$3") (pintype "passive"))
    )
    (net (code "29") (name "GND") (class "Default")
      (node (ref "C1") (pin "2") (pinfunction "2_2") (pintype "passive"))
      (node (ref "C10") (pin "-") (pinfunction "-_-") (pintype "passive"))
      (node (ref "C11") (pin "-") (pinfunction "-_-") (pintype "passive"))
      (node (ref "C12") (pin "2") (pinfunction "2_2") (pintype "passive"))
      (node (ref "C2") (pin "1") (pinfunction "1_1") (pintype "passive"))
      (node (ref "C3") (pin "1") (pinfunction "1_1") (pintype "passive"))
      (node (ref "C4") (pin "-") (pinfunction "-_-") (pintype "passive"))
      (node (ref "C5") (pin "2") (pinfunction "2_2") (pintype "passive"))
      (node (ref "C6") (pin "2") (pinfunction "2_2") (pintype "passive"))
      (node (ref "C7") (pin "-") (pinfunction "-_-") (pintype "passive"))
      (node (ref "C8") (pin "2") (pinfunction "2_2") (pintype "passive"))
      (node (ref "C9") (pin "2") (pinfunction "2_2") (pintype "passive"))
      (node (ref "D1") (pin "A") (pinfunction "A_A") (pintype "passive"))
      (node (ref "D2") (pin "A") (pinfunction "A_A") (pintype "passive"))
      (node (ref "IC1") (pin "1") (pinfunction "GND_1") (pintype "bidirectional"))
      (node (ref "IC2") (pin "1") (pinfunction "GND_1") (pintype "power_in"))
      (node (ref "IC3") (pin "7") (pinfunction "VSS_7") (pintype "power_in"))
      (node (ref "IC4") (pin "7") (pinfunction "VSS_7") (pintype "power_in"))
      (node (ref "IC6") (pin "2") (pinfunction "GROUND_2") (pintype "bidirectional"))
      (node (ref "IC8") (pin "7") (pinfunction "VSS_7") (pintype "power_in"))
      (node (ref "IC9") (pin "4") (pinfunction "~{G2A}_4") (pintype "bidirectional"))
      (node (ref "IC9") (pin "5") (pinfunction "~{G2B}_5") (pintype "bidirectional"))
      (node (ref "IC9") (pin "8") (pinfunction "GND_8") (pintype "bidirectional"))
      (node (ref "K1") (pin "2") (pinfunction "K_2") (pintype "passive"))
      (node (ref "LED->1") (pin "C") (pinfunction "C_C") (pintype "passive"))
      (node (ref "LED->2") (pin "C") (pinfunction "C_C") (pintype "passive"))
      (node (ref "LED->3") (pin "C") (pinfunction "C_C") (pintype "passive"))
      (node (ref "LED->4") (pin "C") (pinfunction "C_C") (pintype "passive"))
      (node (ref "LED->5") (pin "C") (pinfunction "C_C") (pintype "passive"))
      (node (ref "LED->6") (pin "C") (pinfunction "C_C") (pintype "passive"))
      (node (ref "LED->95") (pin "C") (pinfunction "C_C") (pintype "passive"))
      (node (ref "R15") (pin "2") (pinfunction "2_2") (pintype "passive"))
      (node (ref "R16") (pin "1") (pinfunction "1_1") (pintype "passive"))
      (node (ref "R18") (pin "1") (pinfunction "1_1") (pintype "passive"))
      (node (ref "R2") (pin "1") (pinfunction "1_1") (pintype "passive"))
      (node (ref "R21") (pin "1") (pinfunction "1_1") (pintype "passive"))
      (node (ref "R22") (pin "1") (pinfunction "1_1") (pintype "passive"))
      (node (ref "R23") (pin "2") (pinfunction "2_2") (pintype "passive"))
      (node (ref "R25") (pin "1") (pinfunction "1_1") (pintype "passive"))
      (node (ref "R27") (pin "1") (pinfunction "1_1") (pintype "passive"))
      (node (ref "R3") (pin "1") (pinfunction "1_1") (pintype "passive"))
      (node (ref "R30") (pin "1") (pinfunction "1_1") (pintype "passive"))
      (node (ref "R33") (pin "1") (pinfunction "1_1") (pintype "passive"))
      (node (ref "R35") (pin "1") (pinfunction "1_1") (pintype "passive"))
      (node (ref "R37") (pin "1") (pinfunction "1_1") (pintype "passive"))
      (node (ref "R39") (pin "2") (pinfunction "2_2") (pintype "passive"))
      (node (ref "R4") (pin "1") (pinfunction "1_1") (pintype "passive"))
      (node (ref "R41") (pin "1") (pinfunction "1_1") (pintype "passive"))
      (node (ref "R43") (pin "1") (pinfunction "1_1") (pintype "passive"))
      (node (ref "R45") (pin "1") (pinfunction "1_1") (pintype "passive"))
      (node (ref "SI1") (pin "G") (pinfunction "G_G") (pintype "bidirectional"))
      (node (ref "SI4") (pin "G") (pinfunction "G_G") (pintype "bidirectional"))
      (node (ref "U$1") (pin "4") (pinfunction "V-_4") (pintype "power_in"))
      (node (ref "U$2") (pin "P$2") (pinfunction "P2_P$2") (pintype "bidirectional"))
      (node (ref "U$9") (pin "V-") (pinfunction "V-_V-") (pintype "bidirectional"))
      (node (ref "U1") (pin "11") (pinfunction "VCC-_11") (pintype "power_in"))
      (node (ref "U2") (pin "1") (pinfunction "B_1") (pintype "input"))
      (node (ref "U2") (pin "10") (pinfunction "C_10") (pintype "input"))
      (node (ref "U2") (pin "15") (pinfunction "A_15") (pintype "input"))
      (node (ref "U2") (pin "8") (pinfunction "GND_8") (pintype "power_in"))
      (node (ref "U2") (pin "9") (pinfunction "D_9") (pintype "input"))
      (node (ref "X2") (pin "P$12") (pinfunction "12_P$12") (pintype "passive"))
    )
    (net (code "30") (name "HV_RESET") (class "Default")
      (node (ref "BMS-CONN7") (pin "P$1") (pinfunction "1_P$1") (pintype "passive"))
      (node (ref "IC8") (pin "3") (pinfunction "O_3") (pintype "output"))
    )
    (net (code "31") (name "HV_RESET_CP") (class "Default")
      (node (ref "BMS-CONN7") (pin "P$2") (pinfunction "2_P$2") (pintype "passive"))
      (node (ref "IC4") (pin "9") (pinfunction "I1_9") (pintype "input"))
    )
    (net (code "32") (name "HV_RESET_SP") (class "Default")
      (node (ref "BMS-CONN7") (pin "P$3") (pinfunction "3_P$3") (pintype "passive"))
      (node (ref "IC8") (pin "6") (pinfunction "I1_6") (pintype "input"))
    )
    (net (code "33") (name "INIT_CHK_INV") (class "Default")
      (node (ref "IC8") (pin "5") (pinfunction "I0_5") (pintype "input"))
      (node (ref "U1") (pin "3") (pinfunction "NON-INVERTING_INPUT1_3") (pintype "input"))
    )
    (net (code "34") (name "INIT_CHK_INV_12V") (class "Default")
      (node (ref "IC8") (pin "13") (pinfunction "I1_13") (pintype "input"))
      (node (ref "K1") (pin "4") (pinfunction "DS1_4") (pintype "passive"))
      (node (ref "U1") (pin "1") (pinfunction "OUTPUT1_1") (pintype "output"))
    )
    (net (code "35") (name "INSPECTION") (class "Default")
      (node (ref "R10") (pin "1") (pinfunction "1_1") (pintype "passive"))
      (node (ref "R26") (pin "1") (pinfunction "1_1") (pintype "passive"))
      (node (ref "R27") (pin "2") (pinfunction "2_2") (pintype "passive"))
      (node (ref "U$16") (pin "S") (pinfunction "S_S") (pintype "bidirectional"))
    )
    (net (code "36") (name "INSPECTION_IN") (class "Default")
      (node (ref "IC9") (pin "10") (pinfunction "Y5_10") (pintype "bidirectional"))
      (node (ref "R26") (pin "2") (pinfunction "2_2") (pintype "passive"))
      (node (ref "U$16") (pin "G") (pinfunction "G_G") (pintype "bidirectional"))
    )
    (net (code "37") (name "K2_RES") (class "Default")
      (node (ref "BMS-CONN7") (pin "P$6") (pinfunction "6_P$6") (pintype "passive"))
    )
    (net (code "38") (name "K3_RES") (class "Default")
      (node (ref "BMS-CONN7") (pin "P$5") (pinfunction "5_P$5") (pintype "passive"))
    )
    (net (code "39") (name "MANUAL_DRIVING") (class "Default")
      (node (ref "IC3") (pin "13") (pinfunction "I1_13") (pintype "input"))
      (node (ref "R11") (pin "1") (pinfunction "1_1") (pintype "passive"))
      (node (ref "R29") (pin "2") (pinfunction "2_2") (pintype "passive"))
      (node (ref "R44") (pin "1") (pinfunction "1_1") (pintype "passive"))
      (node (ref "R45") (pin "2") (pinfunction "2_2") (pintype "passive"))
      (node (ref "SI6") (pin "G") (pinfunction "G_G") (pintype "bidirectional"))
      (node (ref "U$19") (pin "S") (pinfunction "S_S") (pintype "bidirectional"))
    )
    (net (code "40") (name "MANUAL_DRIVING_IN") (class "Default")
      (node (ref "IC9") (pin "9") (pinfunction "Y6_9") (pintype "bidirectional"))
      (node (ref "R44") (pin "2") (pinfunction "2_2") (pintype "passive"))
      (node (ref "U$19") (pin "G") (pinfunction "G_G") (pintype "bidirectional"))
    )
    (net (code "41") (name "MANUAL_DRIVING_INV") (class "Default")
      (node (ref "IC3") (pin "5") (pinfunction "I0_5") (pintype "input"))
      (node (ref "R30") (pin "2") (pinfunction "2_2") (pintype "passive"))
      (node (ref "SI6") (pin "1") (pinfunction "1_1") (pintype "bidirectional"))
      (node (ref "SI6") (pin "2") (pinfunction "2_2") (pintype "bidirectional"))
      (node (ref "SI6") (pin "5") (pinfunction "5_5") (pintype "bidirectional"))
      (node (ref "SI6") (pin "6") (pinfunction "6_6") (pintype "bidirectional"))
      (node (ref "SI6") (pin "D") (pinfunction "D0_D") (pintype "bidirectional"))
    )
    (net (code "42") (name "MANUAL_VALVE") (class "Default")
      (node (ref "IC3") (pin "6") (pinfunction "I1_6") (pintype "input"))
      (node (ref "R36") (pin "2") (pinfunction "2_2") (pintype "passive"))
      (node (ref "SI7") (pin "G") (pinfunction "G_G") (pintype "bidirectional"))
      (node (ref "X2") (pin "P$8") (pinfunction "8_P$8") (pintype "passive"))
    )
    (net (code "43") (name "MANUAL_VALVE_INV") (class "Default")
      (node (ref "IC4") (pin "2") (pinfunction "I1_2") (pintype "input"))
      (node (ref "R37") (pin "2") (pinfunction "2_2") (pintype "passive"))
      (node (ref "SI7") (pin "1") (pinfunction "1_1") (pintype "bidirectional"))
      (node (ref "SI7") (pin "2") (pinfunction "2_2") (pintype "bidirectional"))
      (node (ref "SI7") (pin "5") (pinfunction "5_5") (pintype "bidirectional"))
      (node (ref "SI7") (pin "6") (pinfunction "6_6") (pintype "bidirectional"))
      (node (ref "SI7") (pin "D") (pinfunction "D0_D") (pintype "bidirectional"))
    )
    (net (code "44") (name "MISSION_SET") (class "Default")
      (node (ref "U1") (pin "10") (pinfunction "NON-INVERTING_INPUT3_10") (pintype "input"))
    )
    (net (code "45") (name "MISSION_SET_12V") (class "Default")
      (node (ref "IC4") (pin "6") (pinfunction "I1_6") (pintype "input"))
      (node (ref "U1") (pin "8") (pinfunction "OUTPUT3_8") (pintype "output"))
    )
    (net (code "46") (name "Net-(FUSE_1A1-2)") (class "Default")
      (node (ref "FUSE_1A1") (pin "P$2") (pinfunction "2_P$2") (pintype "passive"))
      (node (ref "SI1") (pin "1") (pinfunction "1_1") (pintype "bidirectional"))
      (node (ref "SI1") (pin "2") (pinfunction "2_2") (pintype "bidirectional"))
      (node (ref "SI1") (pin "5") (pinfunction "5_5") (pintype "bidirectional"))
      (node (ref "SI1") (pin "6") (pinfunction "6_6") (pintype "bidirectional"))
      (node (ref "SI1") (pin "D") (pinfunction "D0_D") (pintype "bidirectional"))
    )
    (net (code "47") (name "Net-(FUSE_1A2-2)") (class "Default")
      (node (ref "FUSE_1A2") (pin "P$2") (pinfunction "2_P$2") (pintype "passive"))
      (node (ref "SI4") (pin "1") (pinfunction "1_1") (pintype "bidirectional"))
      (node (ref "SI4") (pin "2") (pinfunction "2_2") (pintype "bidirectional"))
      (node (ref "SI4") (pin "5") (pinfunction "5_5") (pintype "bidirectional"))
      (node (ref "SI4") (pin "6") (pinfunction "6_6") (pintype "bidirectional"))
      (node (ref "SI4") (pin "D") (pinfunction "D0_D") (pintype "bidirectional"))
    )
    (net (code "48") (name "Net-(IC2-CV)") (class "Default")
      (node (ref "C1") (pin "1") (pinfunction "1_1") (pintype "passive"))
      (node (ref "IC2") (pin "5") (pinfunction "CV_5") (pintype "input"))
    )
    (net (code "49") (name "Net-(IC2-DIS)") (class "Default")
      (node (ref "C9") (pin "1") (pinfunction "1_1") (pintype "passive"))
      (node (ref "IC2") (pin "6") (pinfunction "THR_6") (pintype "input"))
      (node (ref "IC2") (pin "7") (pinfunction "DIS_7") (pintype "input"))
    )
    (net (code "50") (name "Net-(IC2-R)") (class "Default")
      (node (ref "C12") (pin "1") (pinfunction "1_1") (pintype "passive"))
      (node (ref "IC2") (pin "4") (pinfunction "R_4") (pintype "input"))
      (node (ref "R31") (pin "1") (pinfunction "1_1") (pintype "passive"))
    )
    (net (code "51") (name "Net-(IC3A-O)") (class "Default")
      (node (ref "IC3") (pin "3") (pinfunction "O_3") (pintype "output"))
      (node (ref "IC3") (pin "8") (pinfunction "I0_8") (pintype "input"))
    )
    (net (code "52") (name "Net-(IC3B-O)") (class "Default")
      (node (ref "IC3") (pin "4") (pinfunction "O_4") (pintype "output"))
      (node (ref "IC3") (pin "9") (pinfunction "I1_9") (pintype "input"))
    )
    (net (code "53") (name "Net-(IC3D-O)") (class "Default")
      (node (ref "IC3") (pin "11") (pinfunction "O_11") (pintype "output"))
      (node (ref "IC4") (pin "1") (pinfunction "I0_1") (pintype "input"))
    )
    (net (code "54") (name "Net-(IC4B-I0)") (class "Default")
      (node (ref "IC4") (pin "5") (pinfunction "I0_5") (pintype "input"))
      (node (ref "IC8") (pin "10") (pinfunction "O_10") (pintype "output"))
    )
    (net (code "55") (name "Net-(IC5-G)") (class "Default")
      (node (ref "IC5") (pin "4") (pinfunction "G_4") (pintype "bidirectional"))
      (node (ref "R9") (pin "2") (pinfunction "2_2") (pintype "passive"))
      (node (ref "U$1") (pin "1") (pinfunction "OUT_1") (pintype "output"))
    )
    (net (code "56") (name "Net-(IC7-G)") (class "Default")
      (node (ref "IC7") (pin "4") (pinfunction "G_4") (pintype "bidirectional"))
      (node (ref "R8") (pin "2") (pinfunction "2_2") (pintype "passive"))
      (node (ref "U$1") (pin "7") (pinfunction "OUT_7") (pintype "output"))
    )
    (net (code "57") (name "Net-(K1-A)") (class "Default")
      (node (ref "K1") (pin "1") (pinfunction "A_1") (pintype "passive"))
      (node (ref "R14") (pin "1") (pinfunction "1_1") (pintype "passive"))
    )
    (net (code "58") (name "Net-(LED->1-PadA)") (class "Default")
      (node (ref "LED->1") (pin "A") (pinfunction "A_A") (pintype "passive"))
      (node (ref "R6") (pin "2") (pinfunction "2_2") (pintype "passive"))
    )
    (net (code "59") (name "Net-(LED->2-PadA)") (class "Default")
      (node (ref "LED->2") (pin "A") (pinfunction "A_A") (pintype "passive"))
      (node (ref "R7") (pin "2") (pinfunction "2_2") (pintype "passive"))
    )
    (net (code "60") (name "Net-(LED->3-PadA)") (class "Default")
      (node (ref "LED->3") (pin "A") (pinfunction "A_A") (pintype "passive"))
      (node (ref "R10") (pin "2") (pinfunction "2_2") (pintype "passive"))
    )
    (net (code "61") (name "Net-(LED->4-PadA)") (class "Default")
      (node (ref "LED->4") (pin "A") (pinfunction "A_A") (pintype "passive"))
      (node (ref "R11") (pin "2") (pinfunction "2_2") (pintype "passive"))
    )
    (net (code "62") (name "Net-(LED->5-PadA)") (class "Default")
      (node (ref "LED->5") (pin "A") (pinfunction "A_A") (pintype "passive"))
      (node (ref "R12") (pin "2") (pinfunction "2_2") (pintype "passive"))
    )
    (net (code "63") (name "Net-(LED->6-PadA)") (class "Default")
      (node (ref "LED->6") (pin "A") (pinfunction "A_A") (pintype "passive"))
      (node (ref "R13") (pin "2") (pinfunction "2_2") (pintype "passive"))
    )
    (net (code "64") (name "Net-(LED->95-PadA)") (class "Default")
      (node (ref "LED->95") (pin "A") (pinfunction "A_A") (pintype "passive"))
      (node (ref "R5") (pin "2") (pinfunction "2_2") (pintype "passive"))
    )
    (net (code "65") (name "Net-(U1D-NON-INVERTING_INPUT4)") (class "Default")
      (node (ref "R34") (pin "1") (pinfunction "1_1") (pintype "passive"))
      (node (ref "R38") (pin "1") (pinfunction "1_1") (pintype "passive"))
      (node (ref "R39") (pin "1") (pinfunction "1_1") (pintype "passive"))
      (node (ref "U1") (pin "12") (pinfunction "NON-INVERTING_INPUT4_12") (pintype "input"))
    )
    (net (code "66") (name "Net-(U2-CLR)") (class "Default")
      (node (ref "R23") (pin "1") (pinfunction "1_1") (pintype "passive"))
      (node (ref "U2") (pin "14") (pinfunction "CLR_14") (pintype "input"))
      (node (ref "U2") (pin "7") (pinfunction "QD_7") (pintype "output"))
    )
    (net (code "67") (name "RES_1_IN") (class "Default")
      (node (ref "U$2") (pin "P$3") (pinfunction "P3_P$3") (pintype "bidirectional"))
      (node (ref "U$9") (pin "NC+") (pinfunction "NC+_NC+") (pintype "bidirectional"))
      (node (ref "X2") (pin "P$1") (pinfunction "1_P$1") (pintype "passive"))
    )
    (net (code "68") (name "RES_1_OUT") (class "Default")
      (node (ref "U$9") (pin "NC-") (pinfunction "NC-_NC-") (pintype "bidirectional"))
      (node (ref "X2") (pin "P$2") (pinfunction "2_P$2") (pintype "passive"))
    )
    (net (code "69") (name "SIG1") (class "Default")
      (node (ref "IC3") (pin "10") (pinfunction "O_10") (pintype "output"))
      (node (ref "IC8") (pin "8") (pinfunction "I0_8") (pintype "input"))
    )
    (net (code "70") (name "SIG2") (class "Default")
      (node (ref "IC4") (pin "10") (pinfunction "O_10") (pintype "output"))
      (node (ref "IC8") (pin "1") (pinfunction "I0_1") (pintype "input"))
    )
    (net (code "71") (name "SIG3") (class "Default")
      (node (ref "IC4") (pin "11") (pinfunction "O_11") (pintype "output"))
      (node (ref "IC8") (pin "2") (pinfunction "I1_2") (pintype "input"))
    )
    (net (code "72") (name "SIG4") (class "Default")
      (node (ref "IC4") (pin "3") (pinfunction "O_3") (pintype "output"))
      (node (ref "IC8") (pin "9") (pinfunction "I1_9") (pintype "input"))
    )
    (net (code "73") (name "SIG5") (class "Default")
      (node (ref "IC4") (pin "13") (pinfunction "I1_13") (pintype "input"))
      (node (ref "IC8") (pin "4") (pinfunction "O_4") (pintype "output"))
    )
    (net (code "74") (name "SIG6") (class "Default")
      (node (ref "K1") (pin "3") (pinfunction "DS2_3") (pintype "passive"))
      (node (ref "R15") (pin "1") (pinfunction "1_1") (pintype "passive"))
      (node (ref "R38") (pin "2") (pinfunction "2_2") (pintype "passive"))
    )
    (net (code "75") (name "SKIDPAD") (class "Default")
      (node (ref "R12") (pin "1") (pinfunction "1_1") (pintype "passive"))
      (node (ref "R19") (pin "1") (pinfunction "1_1") (pintype "passive"))
      (node (ref "R22") (pin "2") (pinfunction "2_2") (pintype "passive"))
      (node (ref "U$14") (pin "S") (pinfunction "S_S") (pintype "bidirectional"))
    )
    (net (code "76") (name "SKIDPAD_IN") (class "Default")
      (node (ref "IC9") (pin "14") (pinfunction "Y1_14") (pintype "bidirectional"))
      (node (ref "R19") (pin "2") (pinfunction "2_2") (pintype "passive"))
      (node (ref "U$14") (pin "G") (pinfunction "G_G") (pintype "bidirectional"))
    )
    (net (code "77") (name "TEENSY_IN_BLUE") (class "Default")
      (node (ref "U$1") (pin "6") (pinfunction "-IN_6") (pintype "input"))
    )
    (net (code "78") (name "TEENSY_IN_YELLOW") (class "Default")
      (node (ref "U$1") (pin "3") (pinfunction "+IN_3") (pintype "input"))
    )
    (net (code "79") (name "TRACKDRIVE") (class "Default")
      (node (ref "R28") (pin "1") (pinfunction "1_1") (pintype "passive"))
      (node (ref "R35") (pin "2") (pinfunction "2_2") (pintype "passive"))
      (node (ref "R6") (pin "1") (pinfunction "1_1") (pintype "passive"))
      (node (ref "U$17") (pin "S") (pinfunction "S_S") (pintype "bidirectional"))
    )
    (net (code "80") (name "TRACKDRIVE_IN") (class "Default")
      (node (ref "IC9") (pin "12") (pinfunction "Y3_12") (pintype "bidirectional"))
      (node (ref "R28") (pin "2") (pinfunction "2_2") (pintype "passive"))
      (node (ref "U$17") (pin "G") (pinfunction "G_G") (pintype "bidirectional"))
    )
    (net (code "81") (name "WATCHDOG_IN") (class "Default")
      (node (ref "IC1") (pin "7") (pinfunction "WDI_7") (pintype "bidirectional"))
    )
    (net (code "82") (name "WD_OUT") (class "Default")
      (node (ref "IC1") (pin "5") (pinfunction "~{WDO}_5") (pintype "bidirectional"))
      (node (ref "U1") (pin "5") (pinfunction "NON-INVERTING_INPUT2_5") (pintype "input"))
    )
    (net (code "83") (name "WD_OUT_12V") (class "Default")
      (node (ref "IC3") (pin "1") (pinfunction "I0_1") (pintype "input"))
      (node (ref "U1") (pin "7") (pinfunction "OUTPUT2_7") (pintype "output"))
    )
    (net (code "84") (name "YELLOW_LED") (class "Default")
      (node (ref "IC5") (pin "5") (pinfunction "D_1_5") (pintype "bidirectional"))
      (node (ref "IC5") (pin "6") (pinfunction "D_2_6") (pintype "bidirectional"))
      (node (ref "IC5") (pin "7") (pinfunction "D_3_7") (pintype "bidirectional"))
      (node (ref "IC5") (pin "8") (pinfunction "D_4_8") (pintype "bidirectional"))
      (node (ref "R3") (pin "2") (pinfunction "2_2") (pintype "passive"))
      (node (ref "X2") (pin "P$4") (pinfunction "4_P$4") (pintype "passive"))
    )
    (net (code "85") (name "unconnected-(BMS-CONN7-4-PadP$4)") (class "Default")
      (node (ref "BMS-CONN7") (pin "P$4") (pinfunction "4_P$4") (pintype "passive"))
    )
    (net (code "86") (name "unconnected-(IC1-RP-Pad4)") (class "Default")
      (node (ref "IC1") (pin "4") (pinfunction "RP_4") (pintype "bidirectional"))
    )
    (net (code "87") (name "unconnected-(IC1-RTH-Pad2)") (class "Default")
      (node (ref "IC1") (pin "2") (pinfunction "RTH_2") (pintype "bidirectional"))
    )
    (net (code "88") (name "unconnected-(IC1-WP-Pad6)") (class "Default")
      (node (ref "IC1") (pin "6") (pinfunction "WP_6") (pintype "bidirectional"))
    )
    (net (code "89") (name "unconnected-(IC1-~{RES}-Pad3)") (class "Default")
      (node (ref "IC1") (pin "3") (pinfunction "~{RES}_3") (pintype "bidirectional"))
    )
    (net (code "90") (name "unconnected-(IC9-Y7-Pad7)") (class "Default")
      (node (ref "IC9") (pin "7") (pinfunction "Y7_7") (pintype "bidirectional"))
    )
    (net (code "91") (name "unconnected-(U$3-0-RX1{slash}CRX2-Pad0-RX1)") (class "Default")
      (node (ref "U$3") (pin "0-RX1") (pinfunction "0-RX1/CRX2_0-RX1") (pintype "bidirectional"))
    )
    (net (code "92") (name "unconnected-(U$3-1-TX1{slash}CTX2-Pad1-TX1)") (class "Default")
      (node (ref "U$3") (pin "1-TX1") (pinfunction "1-TX1/CTX2_1-TX1") (pintype "bidirectional"))
    )
    (net (code "93") (name "unconnected-(U$3-4-BCLK1-Pad4-BCLK2)") (class "Default")
      (node (ref "U$3") (pin "4-BCLK2") (pinfunction "4-BCLK1_4-BCLK2") (pintype "bidirectional"))
    )
    (net (code "94") (name "unconnected-(U$3-7-OUT1A{slash}RX2-Pad7-RX2{slash}OUT1A)") (class "Default")
      (node (ref "U$3") (pin "7-RX2/OUT1A") (pinfunction "7-OUT1A/RX2_7-RX2/OUT1A") (pintype "bidirectional"))
    )
    (net (code "95") (name "unconnected-(U$3-8-IN1{slash}TX2-Pad8-TX2{slash}IN1)") (class "Default")
      (node (ref "U$3") (pin "8-TX2/IN1") (pinfunction "8-IN1/TX2_8-TX2/IN1") (pintype "bidirectional"))
    )
    (net (code "96") (name "unconnected-(U$3-10-CS-Pad10-CS{slash}MQSR)") (class "Default")
      (node (ref "U$3") (pin "10-CS/MQSR") (pinfunction "10-CS_10-CS/MQSR") (pintype "bidirectional"))
    )
    (net (code "97") (name "unconnected-(U$3-12-MISO{slash}MQSL-Pad12-MIO{slash}MQSL)") (class "Default")
      (node (ref "U$3") (pin "12-MIO/MQSL") (pinfunction "12-MISO/MQSL_12-MIO/MQSL") (pintype "bidirectional"))
    )
    (net (code "98") (name "unconnected-(U$3-14-A0{slash}TX3{slash}S-PDIF_IN-Pad14-A0{slash}TX3{slash}S-PFI_OUT)") (class "Default")
      (node (ref "U$3") (pin "14-A0/TX3/S-PFI_OUT") (pinfunction "14-A0/TX3/S-PDIF_IN_14-A0/TX3/S-PFI_OUT") (pintype "bidirectional"))
    )
    (net (code "99") (name "unconnected-(U$3-15-A1{slash}RX3{slash}SPDIF_IN-Pad15-A1{slash}RX3{slash}S-PDIF_IN)") (class "Default")
      (node (ref "U$3") (pin "15-A1/RX3/S-PDIF_IN") (pinfunction "15-A1/RX3/SPDIF_IN_15-A1/RX3/S-PDIF_IN") (pintype "bidirectional"))
    )
    (net (code "100") (name "unconnected-(U$3-23-A9{slash}CRX1{slash}MCLK1-Pad23-A9{slash}CRX1{slash}CCLK1)") (class "Default")
      (node (ref "U$3") (pin "23-A9/CRX1/CCLK1") (pinfunction "23-A9/CRX1/MCLK1_23-A9/CRX1/CCLK1") (pintype "bidirectional"))
    )
    (net (code "101") (name "unconnected-(U$3-25-A11{slash}RX6{slash}SDA2-Pad25-A11{slash}SDA2)") (class "Default")
      (node (ref "U$3") (pin "25-A11/SDA2") (pinfunction "25-A11/RX6/SDA2_25-A11/SDA2") (pintype "bidirectional"))
    )
    (net (code "102") (name "unconnected-(U$3-32-OUT1B-Pad32-OUTB1)") (class "Default")
      (node (ref "U$3") (pin "32-OUTB1") (pinfunction "32-OUT1B_32-OUTB1") (pintype "bidirectional"))
    )
    (net (code "103") (name "unconnected-(U$3-Pad2-OUT2)") (class "Default")
      (node (ref "U$3") (pin "2-OUT2") (pinfunction "2-OUT2_2-OUT2") (pintype "bidirectional"))
    )
    (net (code "104") (name "unconnected-(U$3-Pad3-LRCLK2)") (class "Default")
      (node (ref "U$3") (pin "3-LRCLK2") (pinfunction "3-LRCLK2_3-LRCLK2") (pintype "bidirectional"))
    )
    (net (code "105") (name "unconnected-(U$3-Pad3V3-1)") (class "Default")
      (node (ref "U$3") (pin "3V3-1") (pinfunction "3V3-1_3V3-1") (pintype "bidirectional"))
    )
    (net (code "106") (name "unconnected-(U$3-Pad3V3-2)") (class "Default")
      (node (ref "U$3") (pin "3V3-2") (pinfunction "3V3-2_3V3-2") (pintype "bidirectional"))
    )
    (net (code "107") (name "unconnected-(U$3-Pad5-IN2)") (class "Default")
      (node (ref "U$3") (pin "5-IN2") (pinfunction "5-IN2_5-IN2") (pintype "bidirectional"))
    )
    (net (code "108") (name "unconnected-(U$3-Pad6-OUT1D)") (class "Default")
      (node (ref "U$3") (pin "6-OUT1D") (pinfunction "6-OUT1D_6-OUT1D") (pintype "bidirectional"))
    )
    (net (code "109") (name "unconnected-(U$3-Pad9-OUT1C)") (class "Default")
      (node (ref "U$3") (pin "9-OUT1C") (pinfunction "9-OUT1C_9-OUT1C") (pintype "bidirectional"))
    )
    (net (code "110") (name "unconnected-(U$3-Pad11-MOSI{slash}CTX1)") (class "Default")
      (node (ref "U$3") (pin "11-MOSI/CTX1") (pinfunction "11-MOSI/CTX1_11-MOSI/CTX1") (pintype "bidirectional"))
    )
    (net (code "111") (name "unconnected-(U$3-Pad13-SCK{slash}CRX1{slash}LED)") (class "Default")
      (node (ref "U$3") (pin "13-SCK/CRX1/LED") (pinfunction "13-SCK/CRX1/LED_13-SCK/CRX1/LED") (pintype "bidirectional"))
    )
    (net (code "112") (name "unconnected-(U$3-Pad16-A2{slash}RX4{slash}SCL1)") (class "Default")
      (node (ref "U$3") (pin "16-A2/RX4/SCL1") (pinfunction "16-A2/RX4/SCL1_16-A2/RX4/SCL1") (pintype "bidirectional"))
    )
    (net (code "113") (name "unconnected-(U$3-Pad17-A3{slash}TX4{slash}SDA1)") (class "Default")
      (node (ref "U$3") (pin "17-A3/TX4/SDA1") (pinfunction "17-A3/TX4/SDA1_17-A3/TX4/SDA1") (pintype "bidirectional"))
    )
    (net (code "114") (name "unconnected-(U$3-Pad18-A4{slash}SDA0)") (class "Default")
      (node (ref "U$3") (pin "18-A4/SDA0") (pinfunction "18-A4/SDA0_18-A4/SDA0") (pintype "bidirectional"))
    )
    (net (code "115") (name "unconnected-(U$3-Pad19-A5{slash}SCL0)") (class "Default")
      (node (ref "U$3") (pin "19-A5/SCL0") (pinfunction "19-A5/SCL0_19-A5/SCL0") (pintype "bidirectional"))
    )
    (net (code "116") (name "unconnected-(U$3-Pad20-A6{slash}TX5{slash}LRCLK1)") (class "Default")
      (node (ref "U$3") (pin "20-A6/TX5/LRCLK1") (pinfunction "20-A6/TX5/LRCLK1_20-A6/TX5/LRCLK1") (pintype "bidirectional"))
    )
    (net (code "117") (name "unconnected-(U$3-Pad21-A7{slash}RX5{slash}BCLK1)") (class "Default")
      (node (ref "U$3") (pin "21-A7/RX5/BCLK1") (pinfunction "21-A7/RX5/BCLK1_21-A7/RX5/BCLK1") (pintype "bidirectional"))
    )
    (net (code "118") (name "unconnected-(U$3-Pad22-A8{slash}CTX1)") (class "Default")
      (node (ref "U$3") (pin "22-A8/CTX1") (pinfunction "22-A8/CTX1_22-A8/CTX1") (pintype "bidirectional"))
    )
    (net (code "119") (name "unconnected-(U$3-Pad24-A10{slash}TX6{slash}SCL2)") (class "Default")
      (node (ref "U$3") (pin "24-A10/TX6/SCL2") (pinfunction "24-A10/TX6/SCL2_24-A10/TX6/SCL2") (pintype "bidirectional"))
    )
    (net (code "120") (name "unconnected-(U$3-Pad26-A12{slash}MOSI1)") (class "Default")
      (node (ref "U$3") (pin "26-A12/MOSI1") (pinfunction "26-A12/MOSI1_26-A12/MOSI1") (pintype "bidirectional"))
    )
    (net (code "121") (name "unconnected-(U$3-Pad27-A13{slash}SCK1)") (class "Default")
      (node (ref "U$3") (pin "27-A13/SCK1") (pinfunction "27-A13/SCK1_27-A13/SCK1") (pintype "bidirectional"))
    )
    (net (code "122") (name "unconnected-(U$3-Pad28-RX7)") (class "Default")
      (node (ref "U$3") (pin "28-RX7") (pinfunction "28-RX7_28-RX7") (pintype "bidirectional"))
    )
    (net (code "123") (name "unconnected-(U$3-Pad29-TX7)") (class "Default")
      (node (ref "U$3") (pin "29-TX7") (pinfunction "29-TX7_29-TX7") (pintype "bidirectional"))
    )
    (net (code "124") (name "unconnected-(U$3-Pad30-CRX3)") (class "Default")
      (node (ref "U$3") (pin "30-CRX3") (pinfunction "30-CRX3_30-CRX3") (pintype "bidirectional"))
    )
    (net (code "125") (name "unconnected-(U$3-Pad31-CTX3)") (class "Default")
      (node (ref "U$3") (pin "31-CTX3") (pinfunction "31-CTX3_31-CTX3") (pintype "bidirectional"))
    )
    (net (code "126") (name "unconnected-(U$3-Pad33-MCLK2)") (class "Default")
      (node (ref "U$3") (pin "33-MCLK2") (pinfunction "33-MCLK2_33-MCLK2") (pintype "bidirectional"))
    )
    (net (code "127") (name "unconnected-(U$3-PadGND1)") (class "Default")
      (node (ref "U$3") (pin "GND1") (pinfunction "GND1_GND1") (pintype "bidirectional"))
    )
    (net (code "128") (name "unconnected-(U$3-PadGND2)") (class "Default")
      (node (ref "U$3") (pin "GND2") (pinfunction "GND2_GND2") (pintype "bidirectional"))
    )
    (net (code "129") (name "unconnected-(U$3-PadGND3)") (class "Default")
      (node (ref "U$3") (pin "GND3") (pinfunction "GND3_GND3") (pintype "bidirectional"))
    )
    (net (code "130") (name "unconnected-(U$3-PadON{slash}OFF)") (class "Default")
      (node (ref "U$3") (pin "ON/OFF") (pinfunction "ON/OFF_ON/OFF") (pintype "bidirectional"))
    )
    (net (code "131") (name "unconnected-(U$3-PadPROGRAM)") (class "Default")
      (node (ref "U$3") (pin "PROGRAM") (pinfunction "PROGRAM_PROGRAM") (pintype "bidirectional"))
    )
    (net (code "132") (name "unconnected-(U$3-PadVBAT)") (class "Default")
      (node (ref "U$3") (pin "VBAT") (pinfunction "VBAT_VBAT") (pintype "bidirectional"))
    )
    (net (code "133") (name "unconnected-(U$3-PadVIN)") (class "Default")
      (node (ref "U$3") (pin "VIN") (pinfunction "VIN_VIN") (pintype "bidirectional"))
    )
    (net (code "134") (name "unconnected-(U$3-PadVUSB)") (class "Default")
      (node (ref "U$3") (pin "VUSB") (pinfunction "VUSB_VUSB") (pintype "bidirectional"))
    )
    (net (code "135") (name "unconnected-(U2-UP-Pad5)") (class "Default")
      (node (ref "U2") (pin "5") (pinfunction "UP_5") (pintype "passive"))
    )
    (net (code "136") (name "unconnected-(U2-~{BO}-Pad13)") (class "Default")
      (node (ref "U2") (pin "13") (pinfunction "~{BO}_13") (pintype "output"))
    )
    (net (code "137") (name "unconnected-(U2-~{CO}-Pad12)") (class "Default")
      (node (ref "U2") (pin "12") (pinfunction "~{CO}_12") (pintype "output"))
    )
    (net (code "138") (name "unconnected-(X2-6-PadP$6)") (class "Default")
      (node (ref "X2") (pin "P$6") (pinfunction "6_P$6") (pintype "passive"))
    )
  )
)
